# qo-100-pa-bias-controller.net
KiCad netlist of a schematic drawn in EAGLE
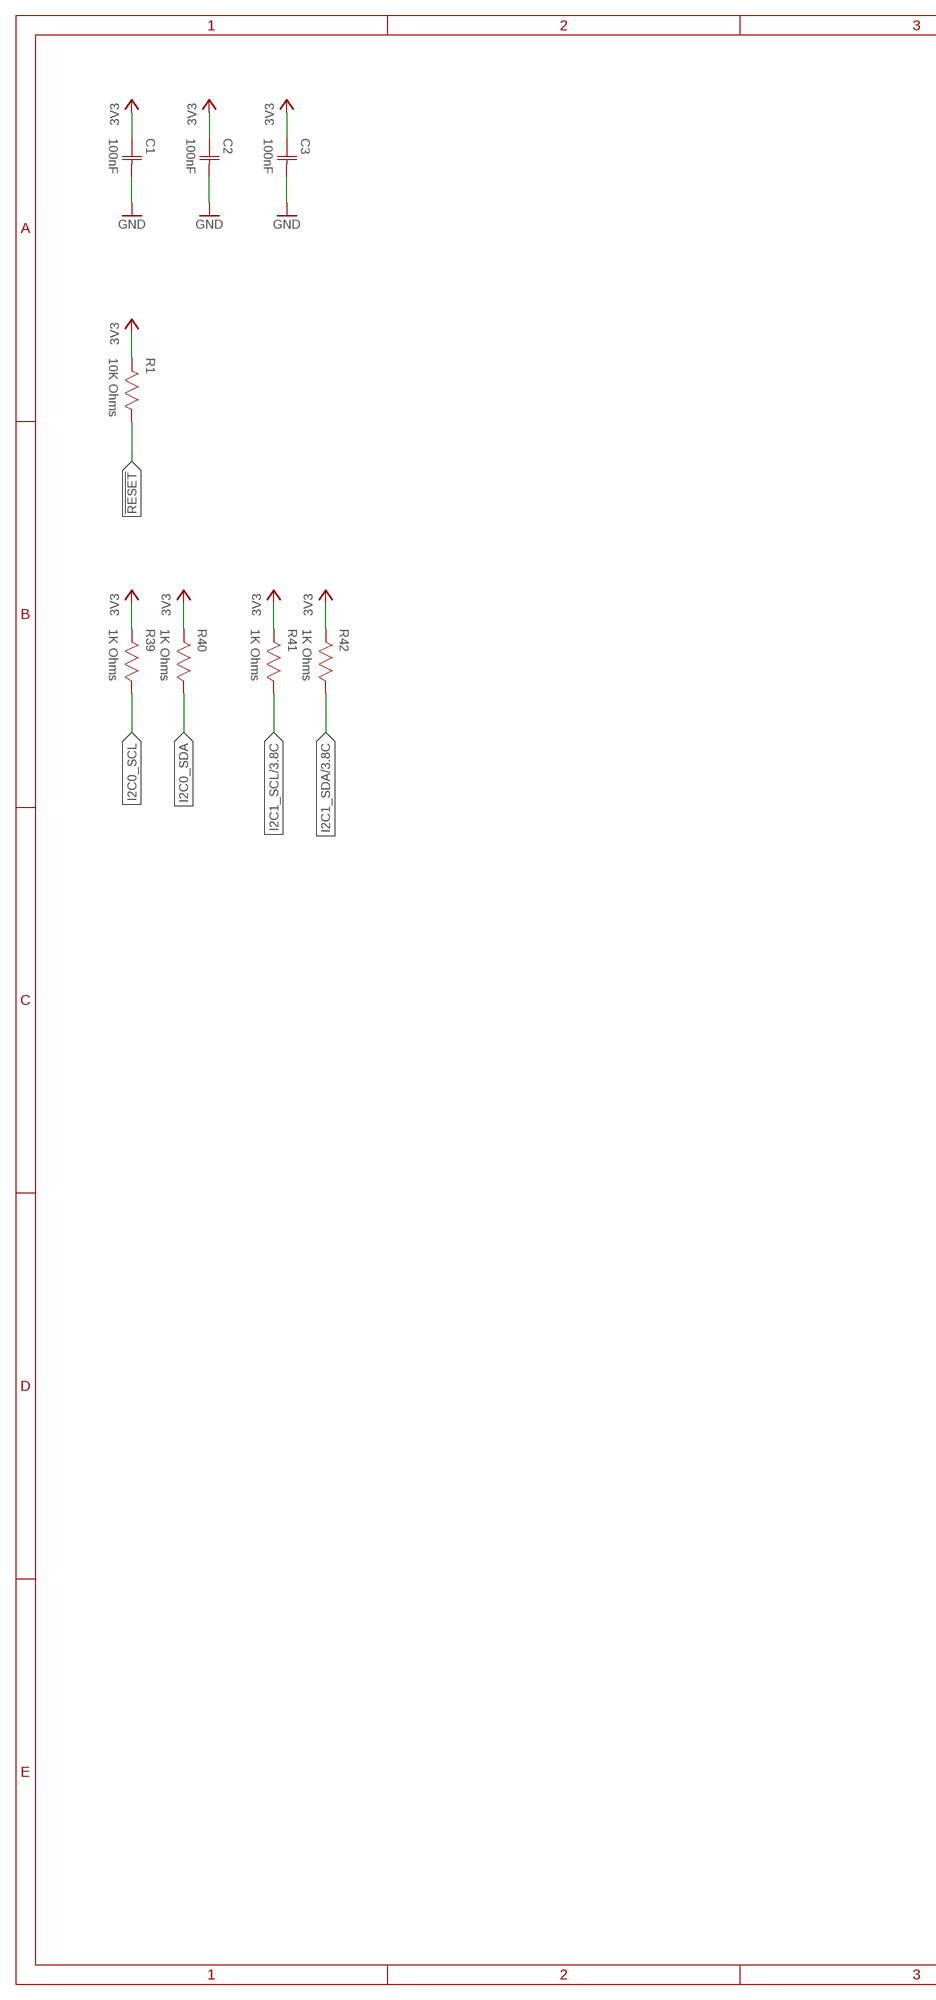
[diagram p0: schematic, sheet 1, part 1 of 2]
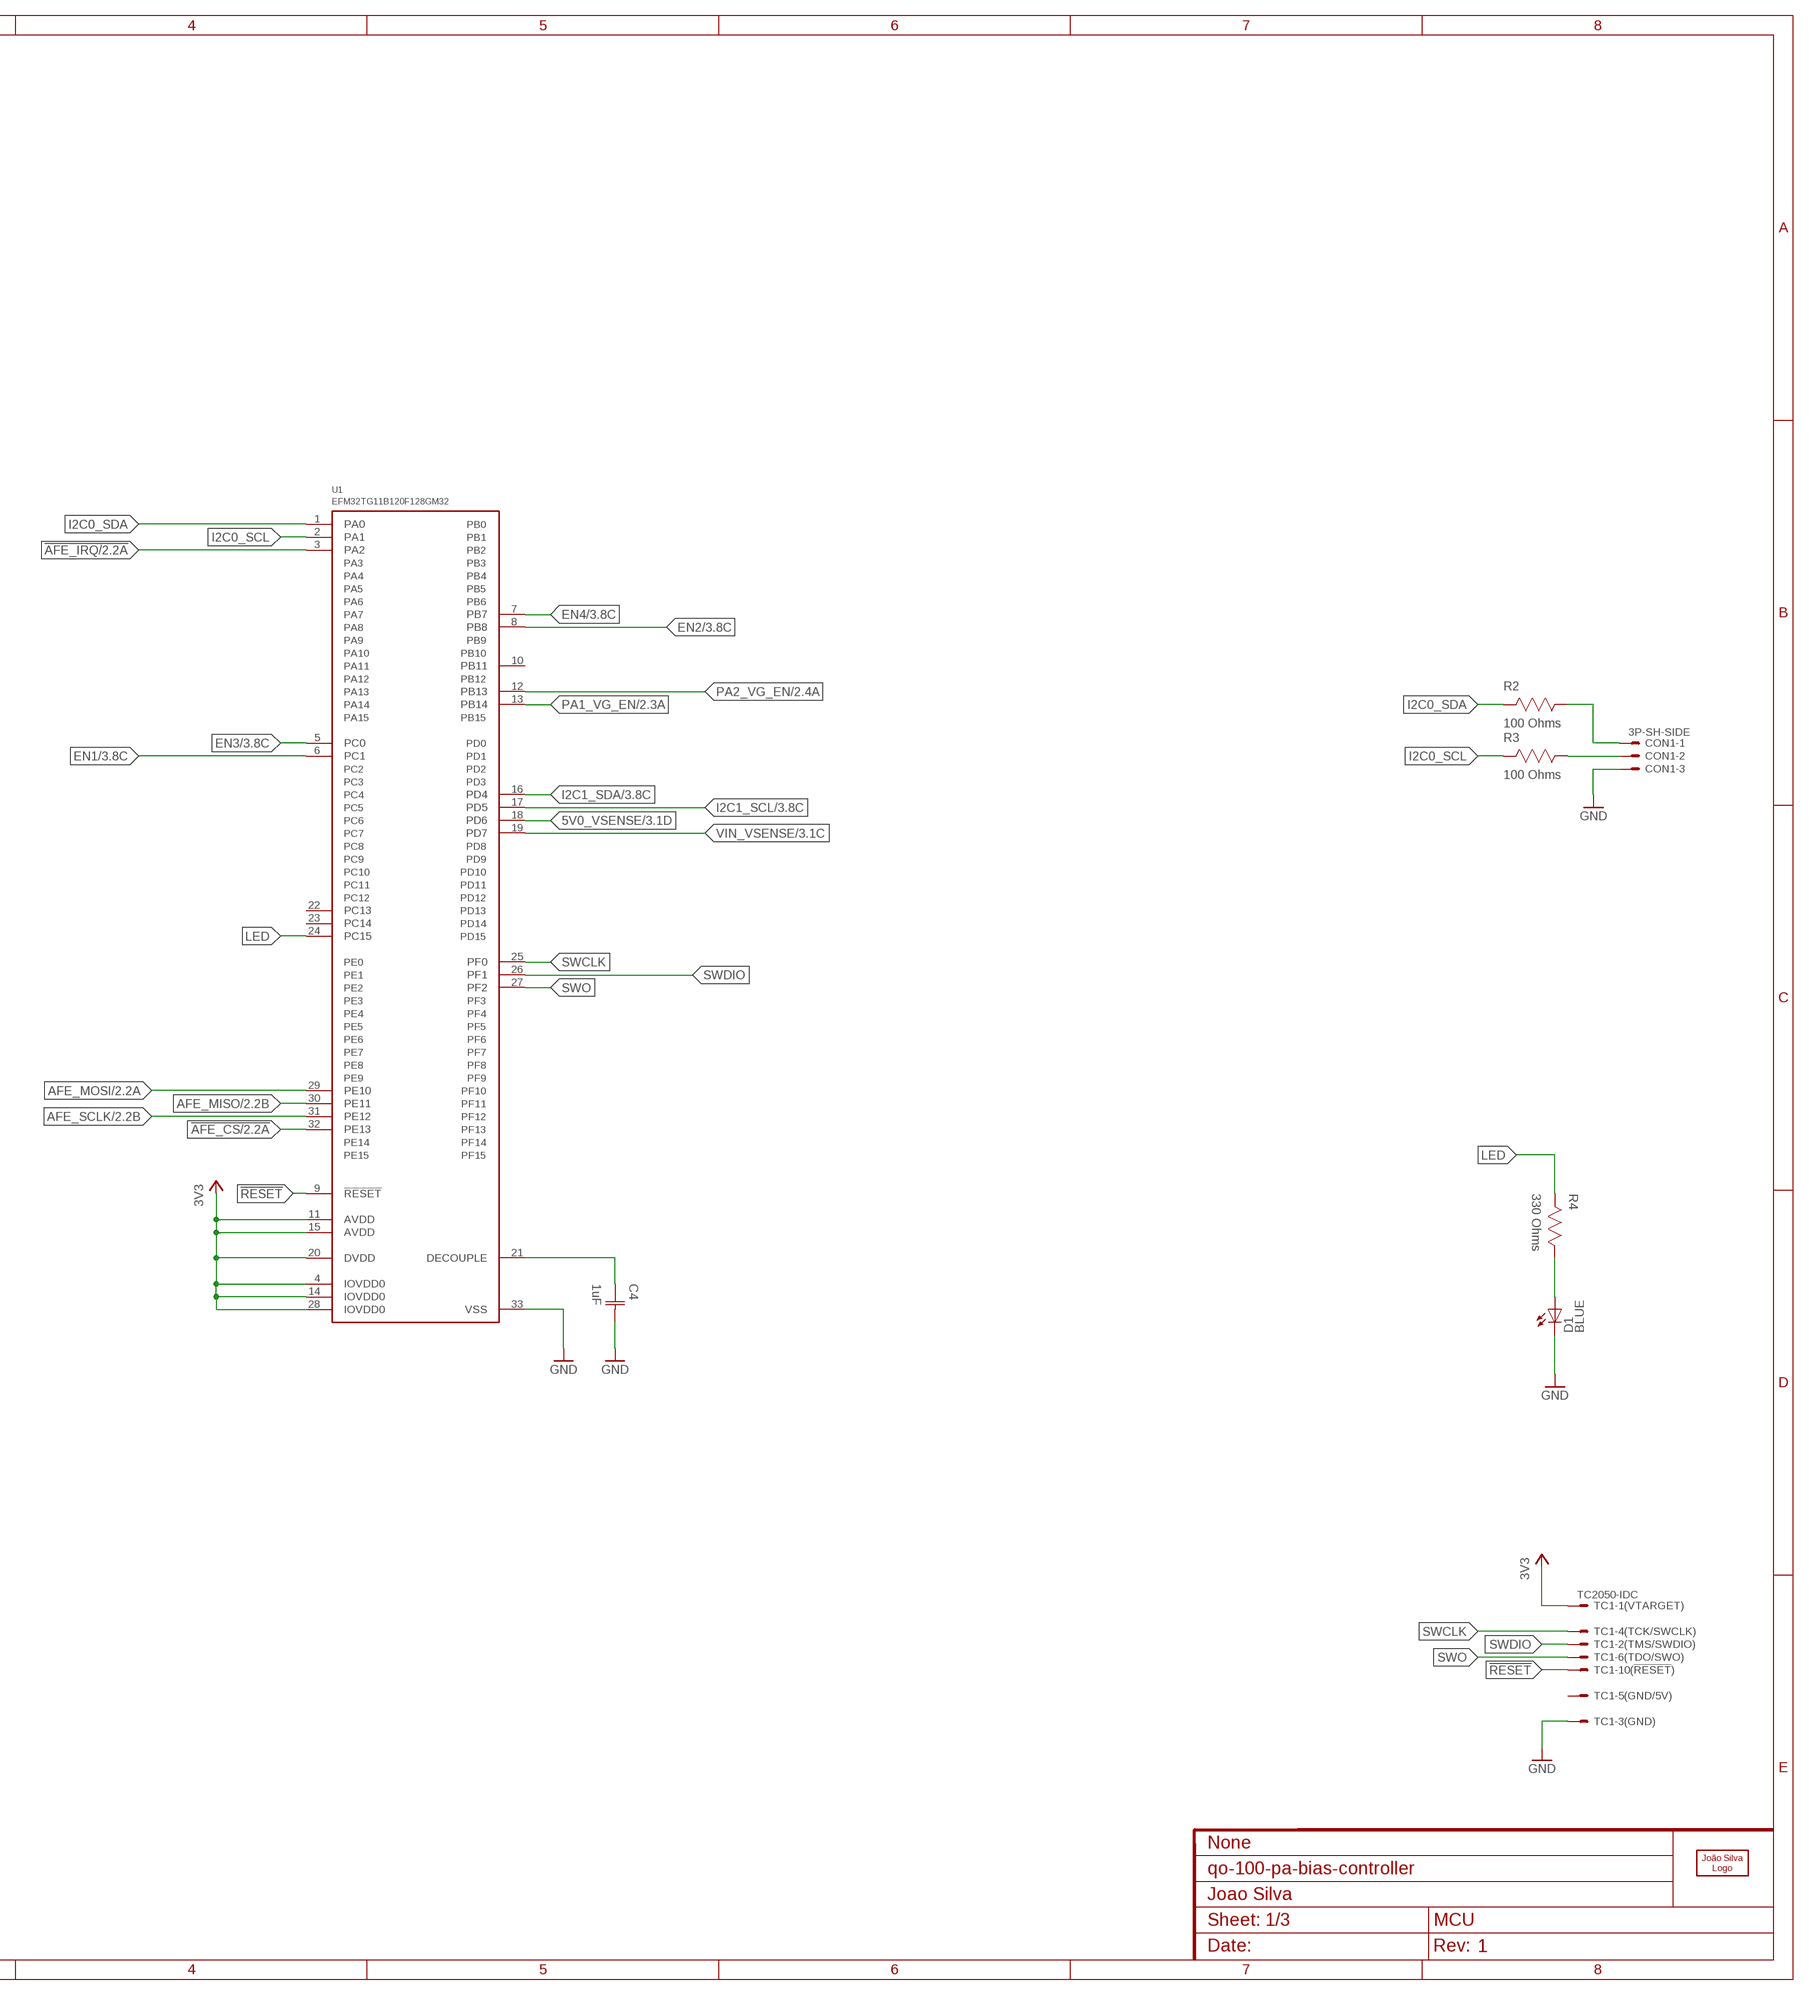
[diagram p1: schematic, sheet 1, part 2 of 2]
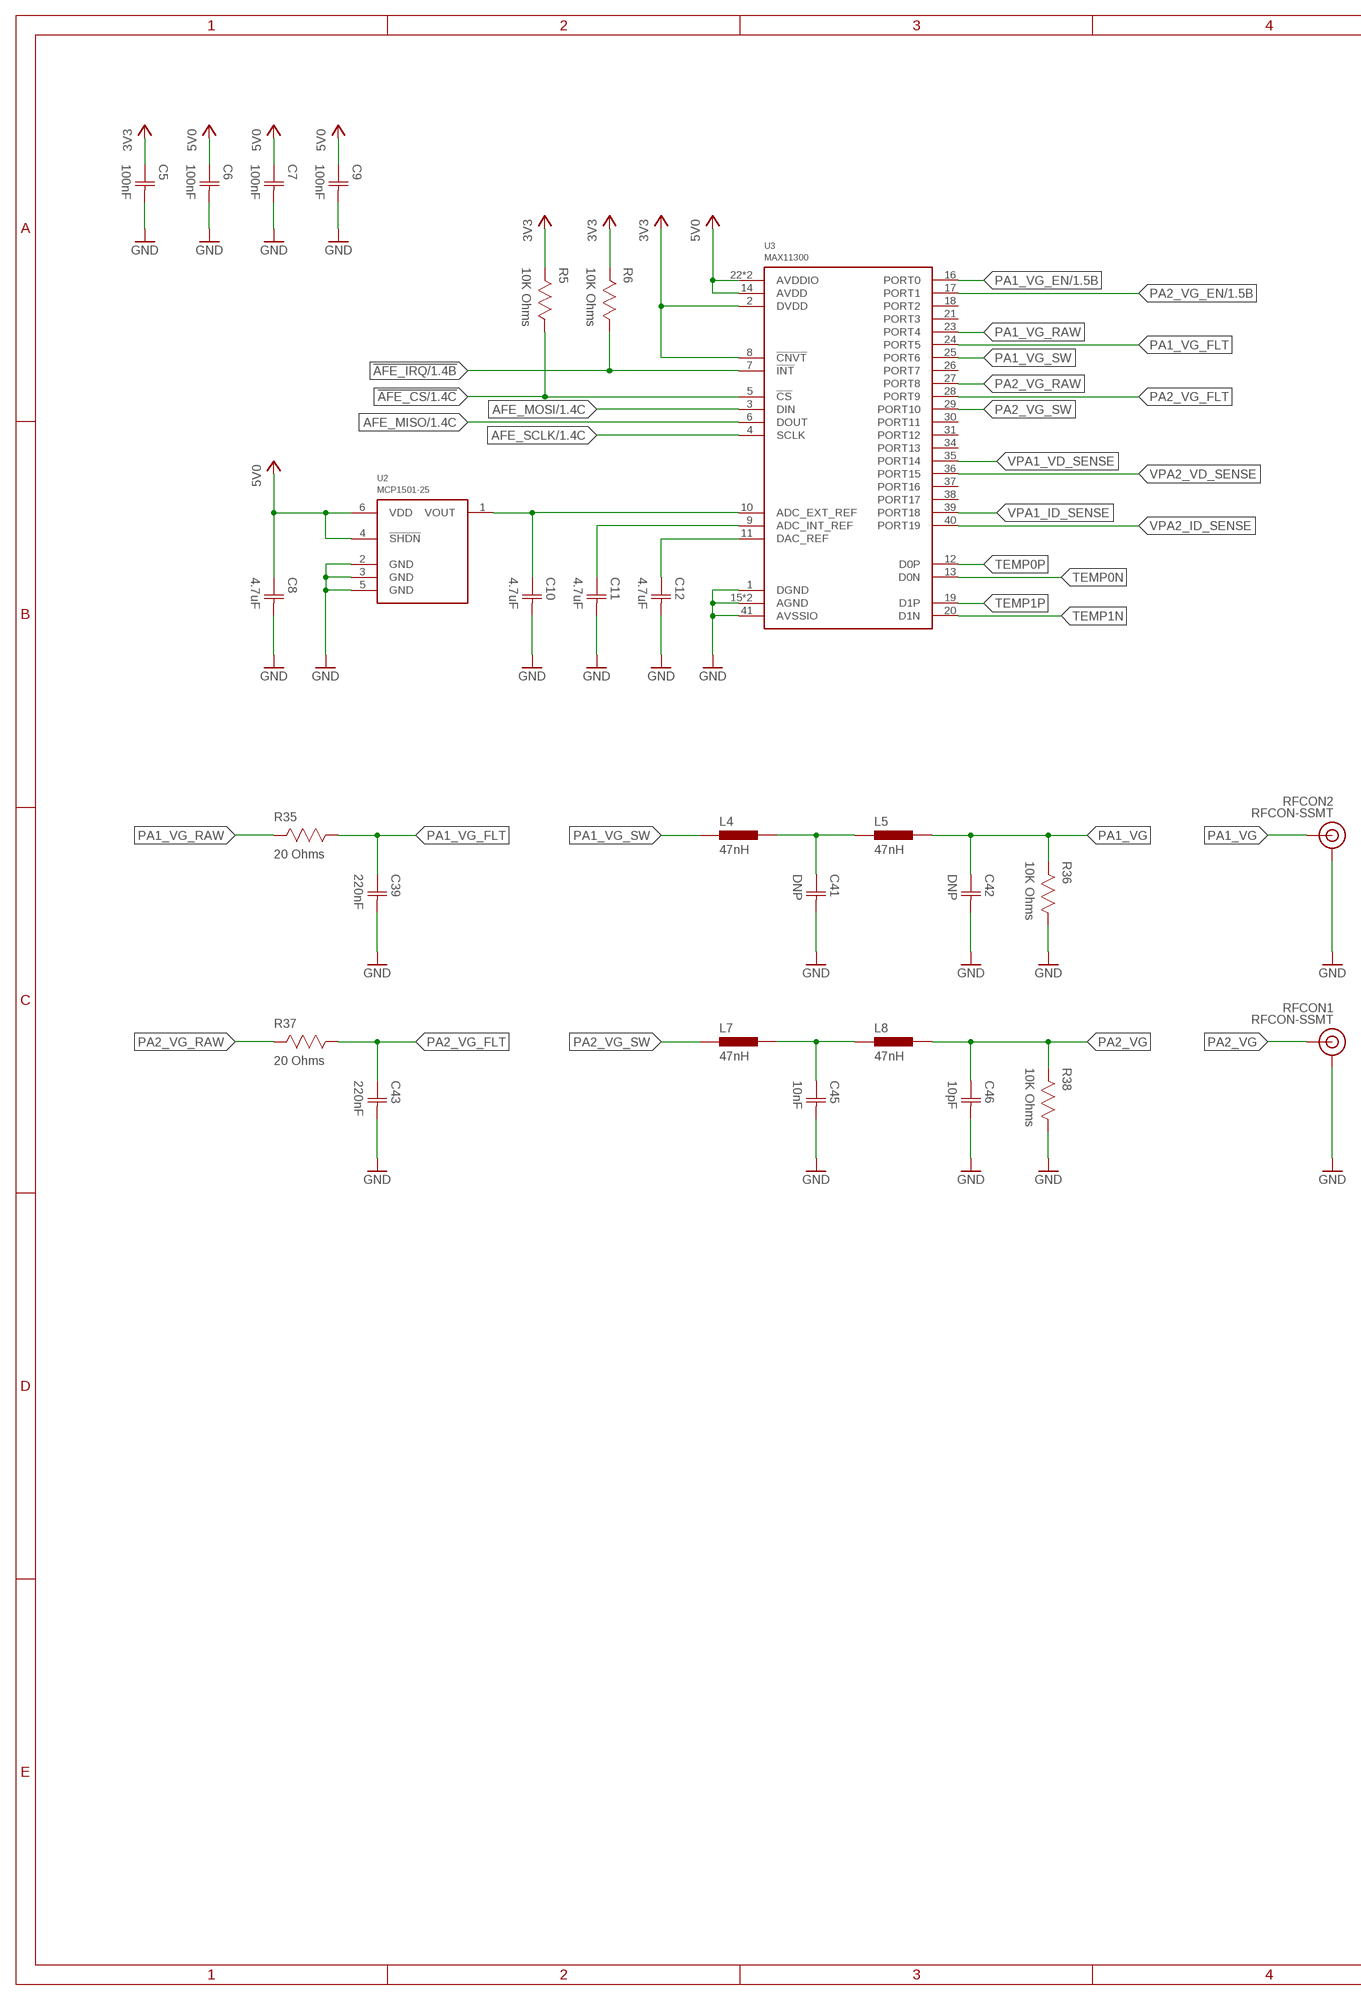
[diagram p2: schematic, sheet 2, part 1 of 2]
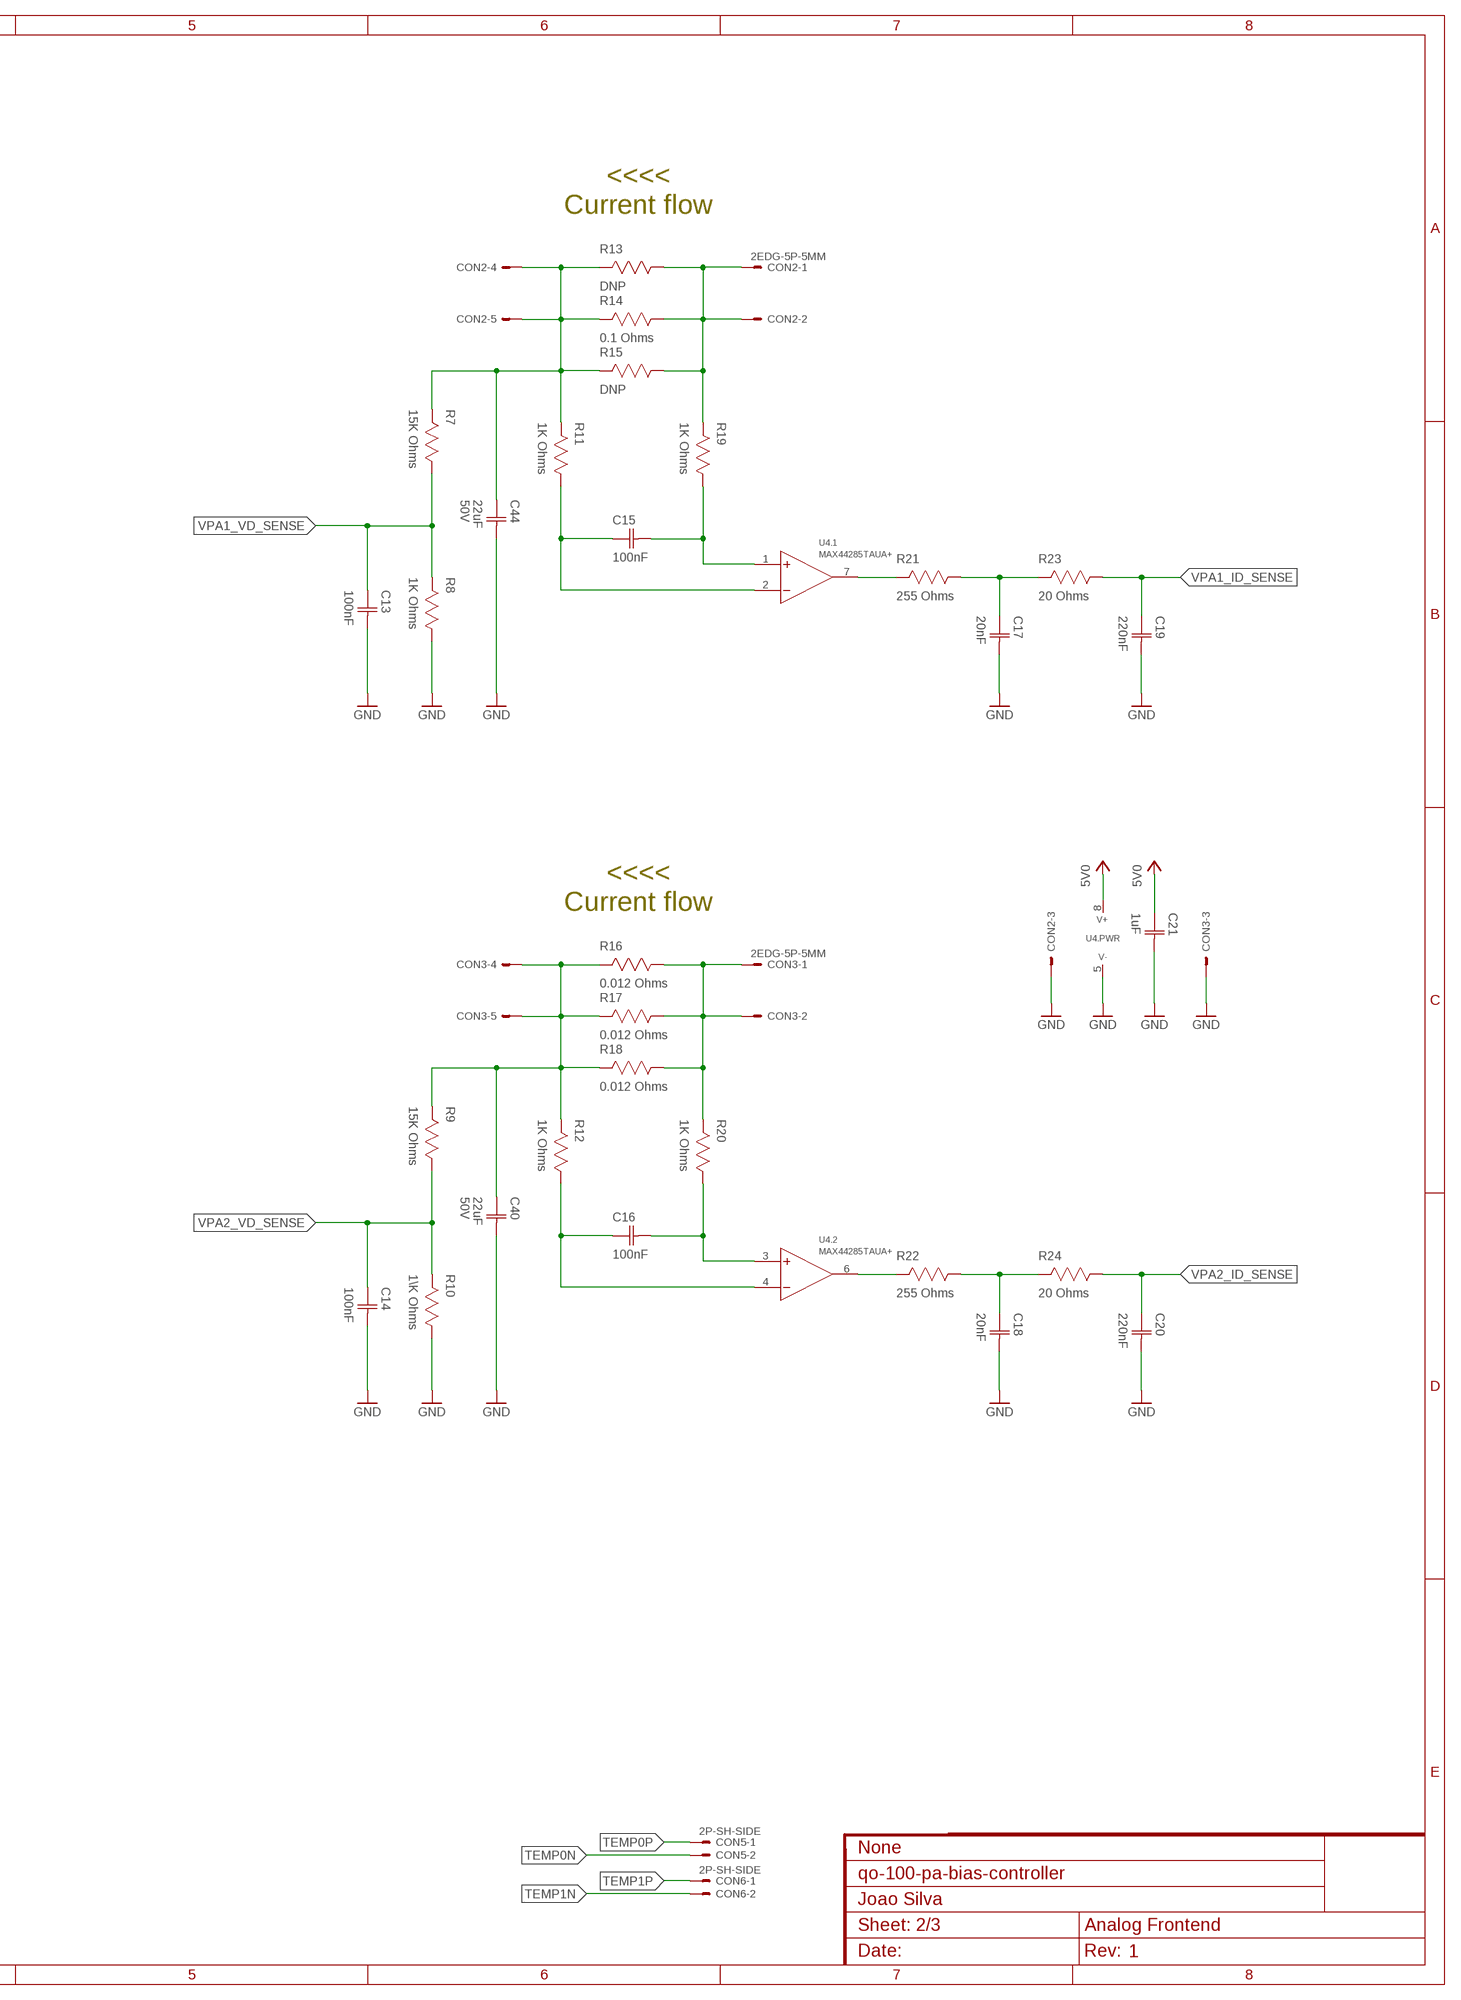
[diagram p3: schematic, sheet 2, part 2 of 2]
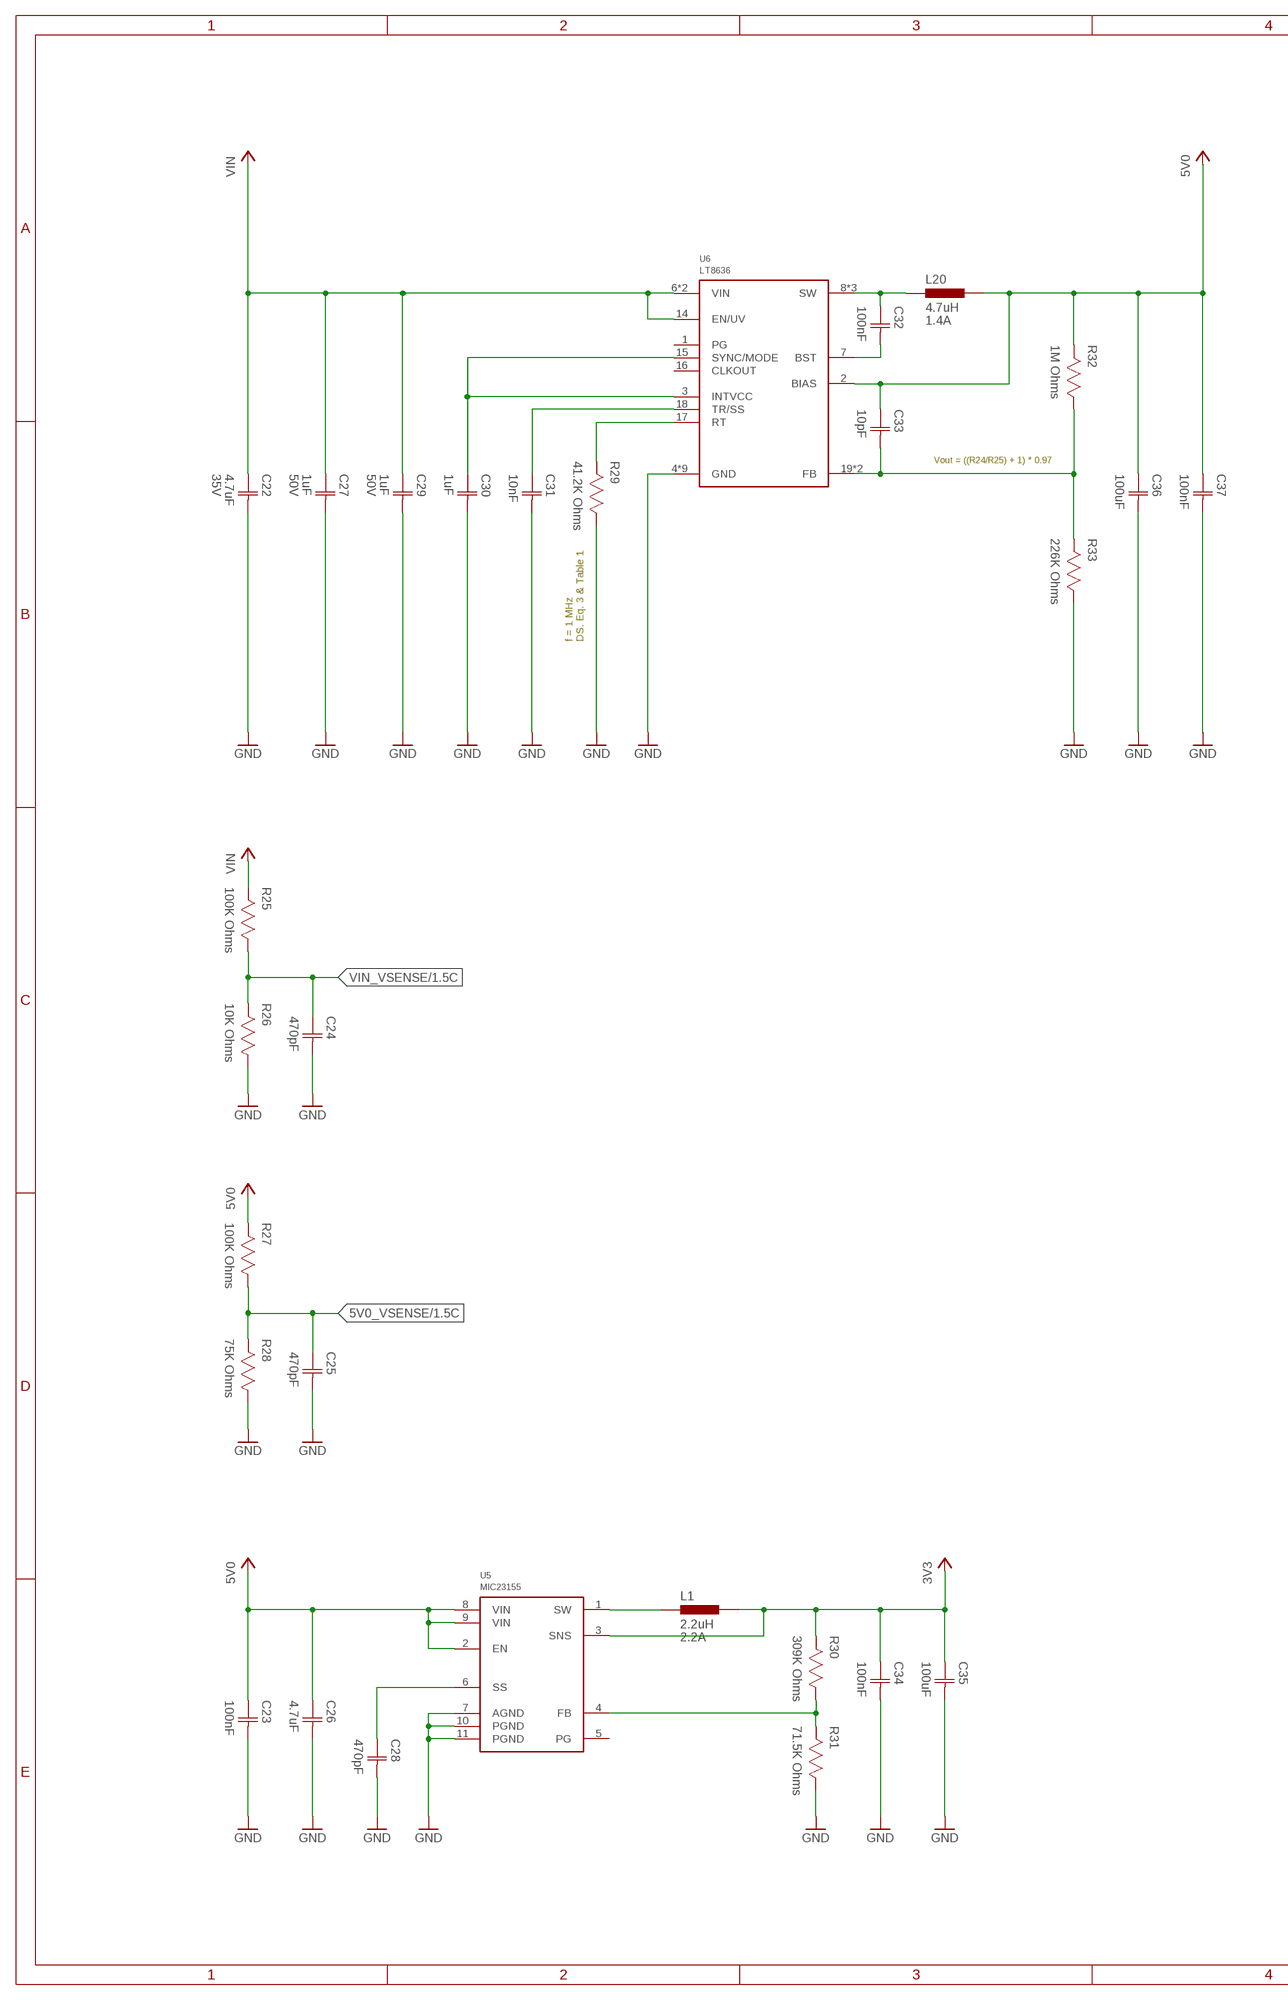
[diagram p4: schematic, sheet 3, part 1 of 2]
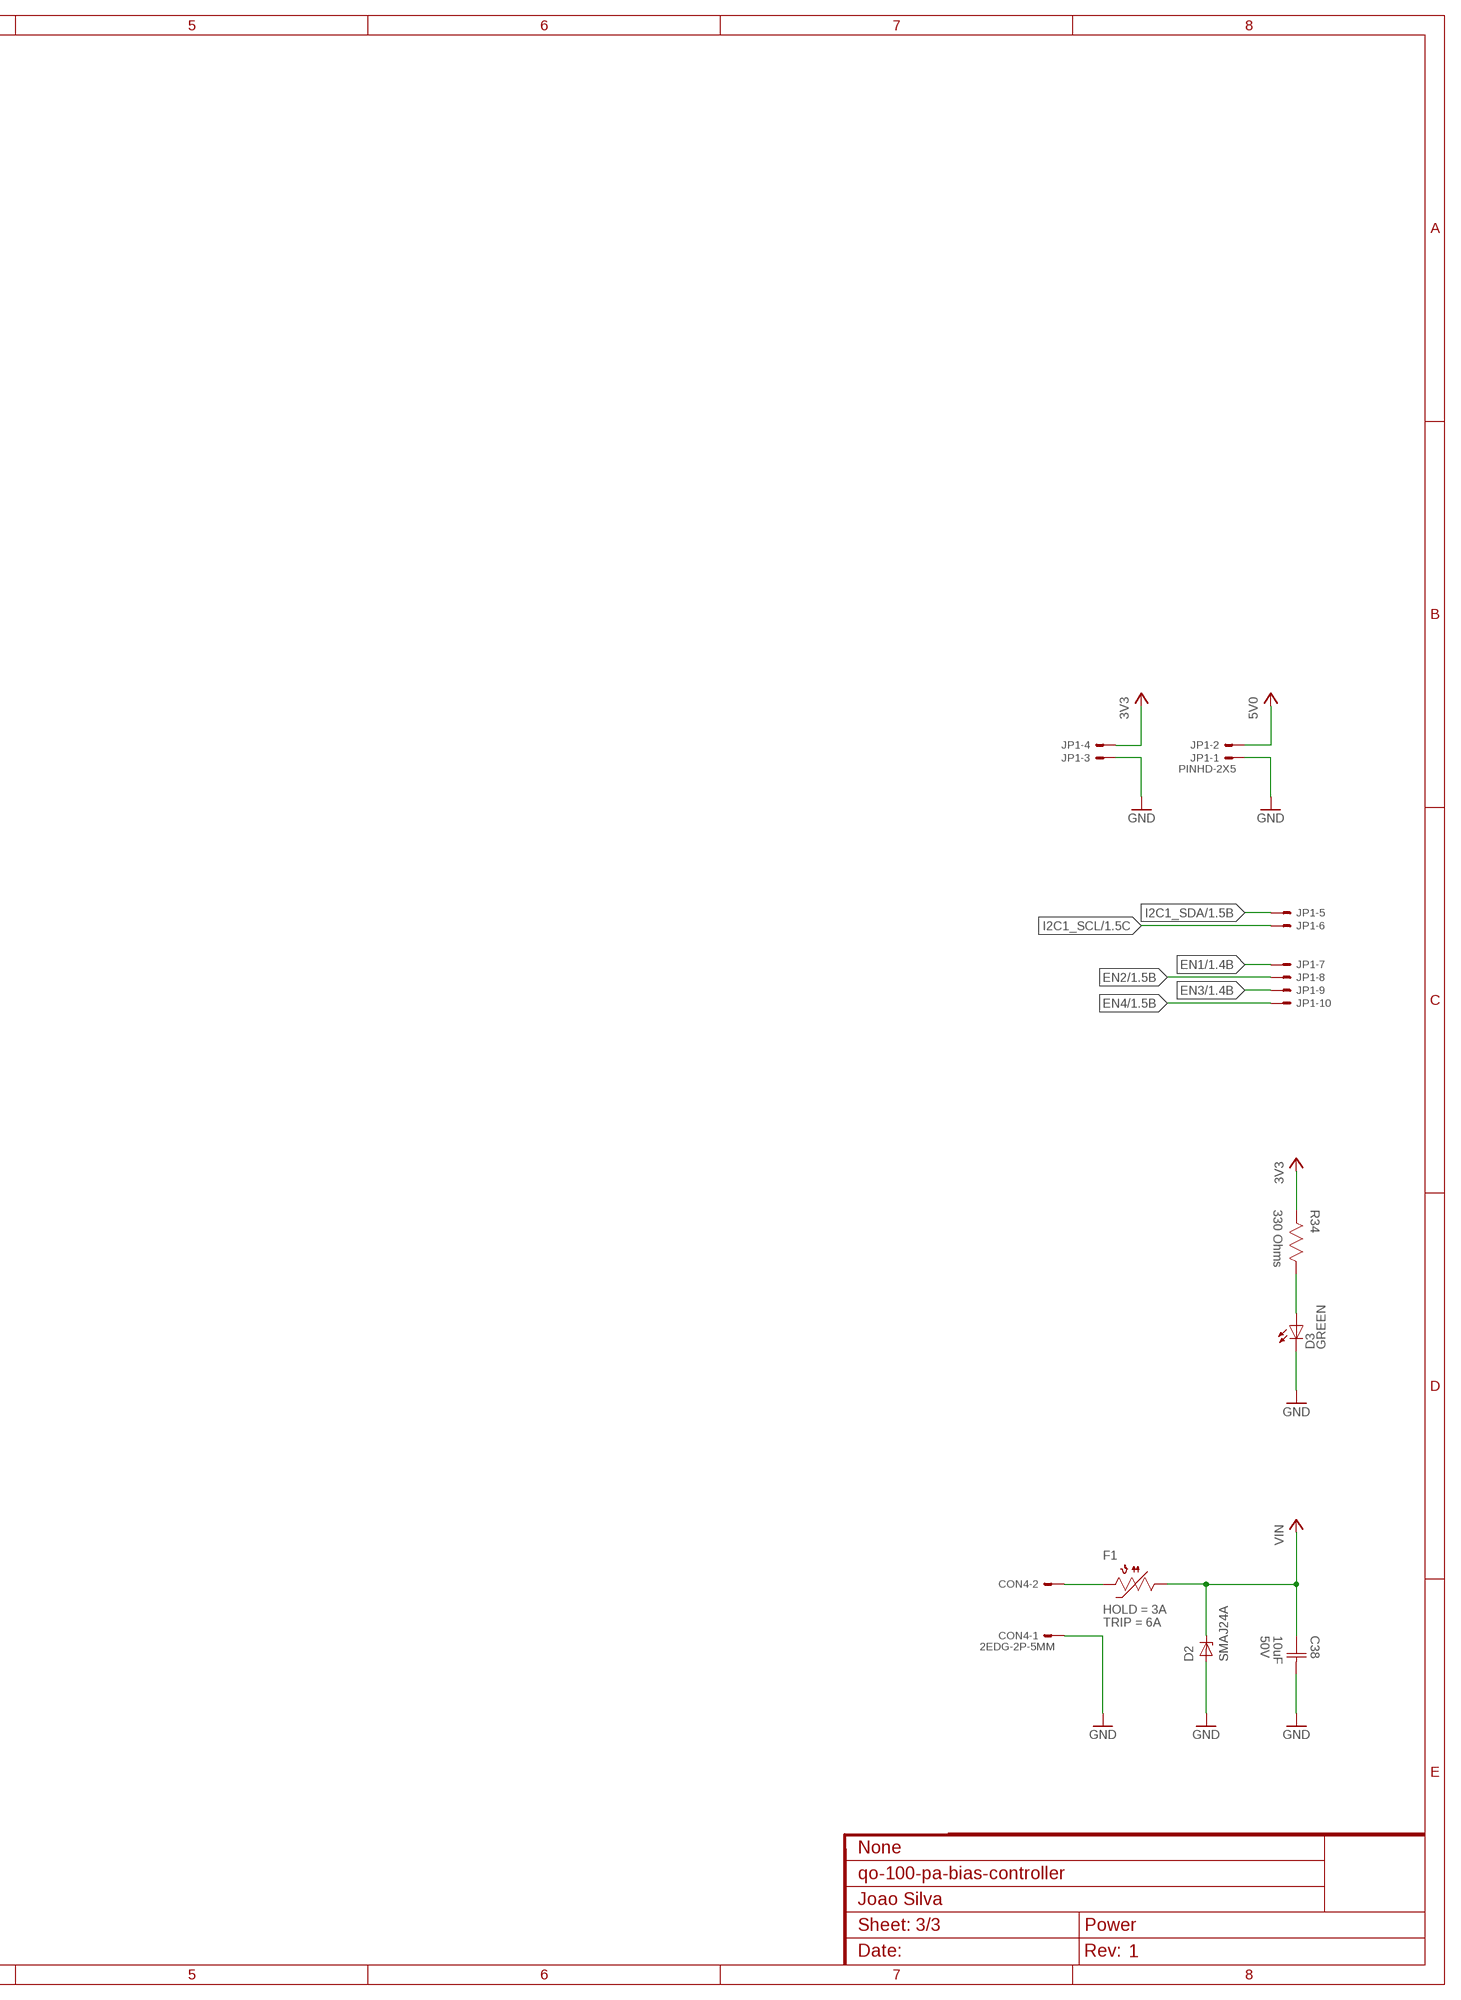
[diagram p5: schematic, sheet 3, part 2 of 2]

(export (version "E")
  (design (tool "Eeschema 10.0.6"))
  (components
    (comp (ref "C5")
      (value "100nF")
      (footprint "eagle-import:CAP0603")
      (libsource (lib "eagle-import") (part "CAPACITOR-0603"))
    )
    (comp (ref "C6")
      (value "100nF")
      (footprint "eagle-import:CAP0603")
      (libsource (lib "eagle-import") (part "CAPACITOR-0603"))
    )
    (comp (ref "C7")
      (value "100nF")
      (footprint "eagle-import:CAP0603")
      (libsource (lib "eagle-import") (part "CAPACITOR-0603"))
    )
    (comp (ref "C8")
      (value "4.7uF")
      (footprint "eagle-import:CAP0603")
      (libsource (lib "eagle-import") (part "CAPACITOR-0603"))
    )
    (comp (ref "C9")
      (value "100nF")
      (footprint "eagle-import:CAP0603")
      (libsource (lib "eagle-import") (part "CAPACITOR-0603"))
    )
    (comp (ref "C10")
      (value "4.7uF")
      (footprint "eagle-import:CAP0603")
      (libsource (lib "eagle-import") (part "CAPACITOR-0603"))
    )
    (comp (ref "C11")
      (value "4.7uF")
      (footprint "eagle-import:CAP0603")
      (libsource (lib "eagle-import") (part "CAPACITOR-0603"))
    )
    (comp (ref "C12")
      (value "4.7uF")
      (footprint "eagle-import:CAP0603")
      (libsource (lib "eagle-import") (part "CAPACITOR-0603"))
    )
    (comp (ref "C13")
      (value "100nF")
      (footprint "eagle-import:CAP0603")
      (libsource (lib "eagle-import") (part "CAPACITOR-0603"))
    )
    (comp (ref "C14")
      (value "100nF")
      (footprint "eagle-import:CAP0603")
      (libsource (lib "eagle-import") (part "CAPACITOR-0603"))
    )
    (comp (ref "C15")
      (value "100nF")
      (footprint "eagle-import:CAP0603")
      (libsource (lib "eagle-import") (part "CAPACITOR-0603"))
    )
    (comp (ref "C16")
      (value "100nF")
      (footprint "eagle-import:CAP0603")
      (libsource (lib "eagle-import") (part "CAPACITOR-0603"))
    )
    (comp (ref "C17")
      (value "20nF")
      (footprint "eagle-import:CAP0603")
      (libsource (lib "eagle-import") (part "CAPACITOR-0603"))
    )
    (comp (ref "C18")
      (value "20nF")
      (footprint "eagle-import:CAP0603")
      (libsource (lib "eagle-import") (part "CAPACITOR-0603"))
    )
    (comp (ref "C19")
      (value "220nF")
      (footprint "eagle-import:CAP0603")
      (libsource (lib "eagle-import") (part "CAPACITOR-0603"))
    )
    (comp (ref "C20")
      (value "220nF")
      (footprint "eagle-import:CAP0603")
      (libsource (lib "eagle-import") (part "CAPACITOR-0603"))
    )
    (comp (ref "C21")
      (value "1uF")
      (footprint "eagle-import:CAP0603")
      (libsource (lib "eagle-import") (part "CAPACITOR-0603"))
    )
    (comp (ref "C39")
      (value "220nF")
      (footprint "eagle-import:CAP0603")
      (libsource (lib "eagle-import") (part "CAPACITOR-0603"))
    )
    (comp (ref "C40")
      (value "22uF")
      (footprint "eagle-import:CAP2220")
      (fields (field (name "VOLTAGE") "50V"))
      (libsource (lib "eagle-import") (part "CAPACITOR-2220"))
    )
    (comp (ref "C41")
      (value "DNP")
      (footprint "eagle-import:CAP0603")
      (libsource (lib "eagle-import") (part "CAPACITOR-0603"))
    )
    (comp (ref "C42")
      (value "DNP")
      (footprint "eagle-import:CAP0603")
      (libsource (lib "eagle-import") (part "CAPACITOR-0603"))
    )
    (comp (ref "C43")
      (value "220nF")
      (footprint "eagle-import:CAP0603")
      (libsource (lib "eagle-import") (part "CAPACITOR-0603"))
    )
    (comp (ref "C44")
      (value "22uF")
      (footprint "eagle-import:CAP2220")
      (fields (field (name "VOLTAGE") "50V"))
      (libsource (lib "eagle-import") (part "CAPACITOR-2220"))
    )
    (comp (ref "C45")
      (value "10nF")
      (footprint "eagle-import:CAP0603")
      (libsource (lib "eagle-import") (part "CAPACITOR-0603"))
    )
    (comp (ref "C46")
      (value "10pF")
      (footprint "eagle-import:CAP0603")
      (libsource (lib "eagle-import") (part "CAPACITOR-0603"))
    )
    (comp (ref "CON2")
      (value "2EDG-5P-5MM")
      (footprint "eagle-import:2EDG-5P-5MM")
      (libsource (lib "eagle-import") (part "2EDG-5P-5MM"))
    )
    (comp (ref "CON3")
      (value "2EDG-5P-5MM")
      (footprint "eagle-import:2EDG-5P-5MM")
      (libsource (lib "eagle-import") (part "2EDG-5P-5MM"))
    )
    (comp (ref "CON5")
      (value "2P-SH-SIDE")
      (footprint "eagle-import:SH-02-SIDE")
      (libsource (lib "eagle-import") (part "2P-SH-SIDE"))
    )
    (comp (ref "CON6")
      (value "2P-SH-SIDE")
      (footprint "eagle-import:SH-02-SIDE")
      (libsource (lib "eagle-import") (part "2P-SH-SIDE"))
    )
    (comp (ref "L4")
      (value "47nH")
      (footprint "eagle-import:IND0603")
      (libsource (lib "eagle-import") (part "INDUCTOR-0603"))
    )
    (comp (ref "L5")
      (value "47nH")
      (footprint "eagle-import:IND0603")
      (libsource (lib "eagle-import") (part "INDUCTOR-0603"))
    )
    (comp (ref "L7")
      (value "47nH")
      (footprint "eagle-import:IND0603")
      (libsource (lib "eagle-import") (part "INDUCTOR-0603"))
    )
    (comp (ref "L8")
      (value "47nH")
      (footprint "eagle-import:IND0603")
      (libsource (lib "eagle-import") (part "INDUCTOR-0603"))
    )
    (comp (ref "R5")
      (value "10K Ohms")
      (footprint "eagle-import:RES0603")
      (libsource (lib "eagle-import") (part "RESISTOR-0603"))
    )
    (comp (ref "R6")
      (value "10K Ohms")
      (footprint "eagle-import:RES0603")
      (libsource (lib "eagle-import") (part "RESISTOR-0603"))
    )
    (comp (ref "R7")
      (value "15K Ohms")
      (footprint "eagle-import:RES0603")
      (libsource (lib "eagle-import") (part "RESISTOR-0603"))
    )
    (comp (ref "R8")
      (value "1K Ohms")
      (footprint "eagle-import:RES0603")
      (libsource (lib "eagle-import") (part "RESISTOR-0603"))
    )
    (comp (ref "R9")
      (value "15K Ohms")
      (footprint "eagle-import:RES0603")
      (libsource (lib "eagle-import") (part "RESISTOR-0603"))
    )
    (comp (ref "R10")
      (value "1\\K Ohms")
      (footprint "eagle-import:RES0603")
      (libsource (lib "eagle-import") (part "RESISTOR-0603"))
    )
    (comp (ref "R11")
      (value "1K Ohms")
      (footprint "eagle-import:RES0603")
      (libsource (lib "eagle-import") (part "RESISTOR-0603"))
    )
    (comp (ref "R12")
      (value "1K Ohms")
      (footprint "eagle-import:RES0603")
      (libsource (lib "eagle-import") (part "RESISTOR-0603"))
    )
    (comp (ref "R13")
      (value "DNP")
      (footprint "eagle-import:RES2512")
      (libsource (lib "eagle-import") (part "RESISTOR-2512"))
    )
    (comp (ref "R14")
      (value "0.1 Ohms")
      (footprint "eagle-import:RES2512")
      (libsource (lib "eagle-import") (part "RESISTOR-2512"))
    )
    (comp (ref "R15")
      (value "DNP")
      (footprint "eagle-import:RES2512")
      (libsource (lib "eagle-import") (part "RESISTOR-2512"))
    )
    (comp (ref "R16")
      (value "0.012 Ohms")
      (footprint "eagle-import:RES2512")
      (libsource (lib "eagle-import") (part "RESISTOR-2512"))
    )
    (comp (ref "R17")
      (value "0.012 Ohms")
      (footprint "eagle-import:RES2512")
      (libsource (lib "eagle-import") (part "RESISTOR-2512"))
    )
    (comp (ref "R18")
      (value "0.012 Ohms")
      (footprint "eagle-import:RES2512")
      (libsource (lib "eagle-import") (part "RESISTOR-2512"))
    )
    (comp (ref "R19")
      (value "1K Ohms")
      (footprint "eagle-import:RES0603")
      (libsource (lib "eagle-import") (part "RESISTOR-0603"))
    )
    (comp (ref "R20")
      (value "1K Ohms")
      (footprint "eagle-import:RES0603")
      (libsource (lib "eagle-import") (part "RESISTOR-0603"))
    )
    (comp (ref "R21")
      (value "255 Ohms")
      (footprint "eagle-import:RES0603")
      (libsource (lib "eagle-import") (part "RESISTOR-0603"))
    )
    (comp (ref "R22")
      (value "255 Ohms")
      (footprint "eagle-import:RES0603")
      (libsource (lib "eagle-import") (part "RESISTOR-0603"))
    )
    (comp (ref "R23")
      (value "20 Ohms")
      (footprint "eagle-import:RES0603")
      (libsource (lib "eagle-import") (part "RESISTOR-0603"))
    )
    (comp (ref "R24")
      (value "20 Ohms")
      (footprint "eagle-import:RES0603")
      (libsource (lib "eagle-import") (part "RESISTOR-0603"))
    )
    (comp (ref "R35")
      (value "20 Ohms")
      (footprint "eagle-import:RES0603")
      (libsource (lib "eagle-import") (part "RESISTOR-0603"))
    )
    (comp (ref "R36")
      (value "10K Ohms")
      (footprint "eagle-import:RES0603")
      (libsource (lib "eagle-import") (part "RESISTOR-0603"))
    )
    (comp (ref "R37")
      (value "20 Ohms")
      (footprint "eagle-import:RES0603")
      (libsource (lib "eagle-import") (part "RESISTOR-0603"))
    )
    (comp (ref "R38")
      (value "10K Ohms")
      (footprint "eagle-import:RES0603")
      (libsource (lib "eagle-import") (part "RESISTOR-0603"))
    )
    (comp (ref "RFCON1")
      (value "RFCON-SSMT")
      (footprint "eagle-import:SSMT")
      (libsource (lib "eagle-import") (part "RFCON-SSMT"))
    )
    (comp (ref "RFCON2")
      (value "RFCON-SSMT")
      (footprint "eagle-import:SSMT")
      (libsource (lib "eagle-import") (part "RFCON-SSMT"))
    )
    (comp (ref "U2")
      (value "MCP1501-25")
      (footprint "eagle-import:SOT23-6")
      (libsource (lib "eagle-import") (part "MCP1501-25"))
    )
    (comp (ref "U3")
      (value "MAX11300")
      (footprint "eagle-import:QFN40")
      (libsource (lib "eagle-import") (part "MAX11300"))
    )
    (comp (ref "U4")
      (value "MAX44285TAUA+")
      (footprint "eagle-import:MSOP8")
      (libsource (lib "eagle-import") (part "MAX44285AUA+T"))
    )
    (comp (ref "C1")
      (value "100nF")
      (footprint "eagle-import:CAP0603")
      (libsource (lib "eagle-import") (part "CAPACITOR-0603"))
    )
    (comp (ref "C2")
      (value "100nF")
      (footprint "eagle-import:CAP0603")
      (libsource (lib "eagle-import") (part "CAPACITOR-0603"))
    )
    (comp (ref "C3")
      (value "100nF")
      (footprint "eagle-import:CAP0603")
      (libsource (lib "eagle-import") (part "CAPACITOR-0603"))
    )
    (comp (ref "C4")
      (value "1uF")
      (footprint "eagle-import:CAP0603")
      (libsource (lib "eagle-import") (part "CAPACITOR-0603"))
    )
    (comp (ref "CON1")
      (value "3P-SH-SIDE")
      (footprint "eagle-import:SH-03-SIDE")
      (libsource (lib "eagle-import") (part "3P-SH-SIDE"))
    )
    (comp (ref "D1")
      (value "LED0603")
      (footprint "eagle-import:0603")
      (fields (field (name "COLOR") "BLUE"))
      (libsource (lib "eagle-import") (part "LED0603"))
    )
    (comp (ref "LOGO1")
      (value "JS-10MM")
      (footprint "eagle-import:JS_10MM")
      (libsource (lib "eagle-import") (part "JS-10MM"))
    )
    (comp (ref "R1")
      (value "10K Ohms")
      (footprint "eagle-import:RES0603")
      (libsource (lib "eagle-import") (part "RESISTOR-0603"))
    )
    (comp (ref "R2")
      (value "100 Ohms")
      (footprint "eagle-import:RES0603")
      (libsource (lib "eagle-import") (part "RESISTOR-0603"))
    )
    (comp (ref "R3")
      (value "100 Ohms")
      (footprint "eagle-import:RES0603")
      (libsource (lib "eagle-import") (part "RESISTOR-0603"))
    )
    (comp (ref "R4")
      (value "330 Ohms")
      (footprint "eagle-import:RES0603")
      (libsource (lib "eagle-import") (part "RESISTOR-0603"))
    )
    (comp (ref "R39")
      (value "1K Ohms")
      (footprint "eagle-import:RES0603")
      (libsource (lib "eagle-import") (part "RESISTOR-0603"))
    )
    (comp (ref "R40")
      (value "1K Ohms")
      (footprint "eagle-import:RES0603")
      (libsource (lib "eagle-import") (part "RESISTOR-0603"))
    )
    (comp (ref "R41")
      (value "1K Ohms")
      (footprint "eagle-import:RES0603")
      (libsource (lib "eagle-import") (part "RESISTOR-0603"))
    )
    (comp (ref "R42")
      (value "1K Ohms")
      (footprint "eagle-import:RES0603")
      (libsource (lib "eagle-import") (part "RESISTOR-0603"))
    )
    (comp (ref "TC1")
      (value "TC2050-IDC")
      (footprint "eagle-import:TC2050-IDC")
      (libsource (lib "eagle-import") (part "TC2050-IDC"))
    )
    (comp (ref "U1")
      (value "EFM32TG11B120F128GM32")
      (footprint "eagle-import:QFN32_0.5P_TG")
      (libsource (lib "eagle-import") (part "EFM32TG11B1M3220F128G"))
    )
    (comp (ref "C22")
      (value "4.7uF")
      (footprint "eagle-import:CAP0603")
      (fields (field (name "VOLTAGE") "35V"))
      (libsource (lib "eagle-import") (part "CAPACITOR-0603"))
    )
    (comp (ref "C23")
      (value "100nF")
      (footprint "eagle-import:CAP0603")
      (libsource (lib "eagle-import") (part "CAPACITOR-0603"))
    )
    (comp (ref "C24")
      (value "470pF")
      (footprint "eagle-import:CAP0603")
      (libsource (lib "eagle-import") (part "CAPACITOR-0603"))
    )
    (comp (ref "C25")
      (value "470pF")
      (footprint "eagle-import:CAP0603")
      (libsource (lib "eagle-import") (part "CAPACITOR-0603"))
    )
    (comp (ref "C26")
      (value "4.7uF")
      (footprint "eagle-import:CAP0603")
      (libsource (lib "eagle-import") (part "CAPACITOR-0603"))
    )
    (comp (ref "C27")
      (value "1uF")
      (footprint "eagle-import:CAP0603")
      (fields (field (name "VOLTAGE") "50V"))
      (libsource (lib "eagle-import") (part "CAPACITOR-0603"))
    )
    (comp (ref "C28")
      (value "470pF")
      (footprint "eagle-import:CAP0603")
      (libsource (lib "eagle-import") (part "CAPACITOR-0603"))
    )
    (comp (ref "C29")
      (value "1uF")
      (footprint "eagle-import:CAP0603")
      (fields (field (name "VOLTAGE") "50V"))
      (libsource (lib "eagle-import") (part "CAPACITOR-0603"))
    )
    (comp (ref "C30")
      (value "1uF")
      (footprint "eagle-import:CAP0603")
      (libsource (lib "eagle-import") (part "CAPACITOR-0603"))
    )
    (comp (ref "C31")
      (value "10nF")
      (footprint "eagle-import:CAP0603")
      (libsource (lib "eagle-import") (part "CAPACITOR-0603"))
    )
    (comp (ref "C32")
      (value "100nF")
      (footprint "eagle-import:CAP0603")
      (libsource (lib "eagle-import") (part "CAPACITOR-0603"))
    )
    (comp (ref "C33")
      (value "10pF")
      (footprint "eagle-import:CAP0603")
      (libsource (lib "eagle-import") (part "CAPACITOR-0603"))
    )
    (comp (ref "C34")
      (value "100nF")
      (footprint "eagle-import:CAP0603")
      (libsource (lib "eagle-import") (part "CAPACITOR-0603"))
    )
    (comp (ref "C35")
      (value "100uF")
      (footprint "eagle-import:CAP1206")
      (libsource (lib "eagle-import") (part "CAPACITOR-1206"))
    )
    (comp (ref "C36")
      (value "100uF")
      (footprint "eagle-import:CAP1206")
      (libsource (lib "eagle-import") (part "CAPACITOR-1206"))
    )
    (comp (ref "C37")
      (value "100nF")
      (footprint "eagle-import:CAP0603")
      (libsource (lib "eagle-import") (part "CAPACITOR-0603"))
    )
    (comp (ref "C38")
      (value "10uF")
      (footprint "eagle-import:CAP1206")
      (fields (field (name "VOLTAGE") "50V"))
      (libsource (lib "eagle-import") (part "CAPACITOR-1206"))
    )
    (comp (ref "CON4")
      (value "2EDG-2P-5MM")
      (footprint "eagle-import:2EDG-2P-5MM")
      (libsource (lib "eagle-import") (part "2EDG-2P-5MM"))
    )
    (comp (ref "D2")
      (value "SMAJ24A")
      (footprint "eagle-import:DO214AC")
      (fields (field (name "MF") "Littelfuse"))
      (libsource (lib "eagle-import") (part "SMAJA24"))
    )
    (comp (ref "D3")
      (value "LED0603")
      (footprint "eagle-import:0603")
      (fields (field (name "COLOR") "GREEN"))
      (libsource (lib "eagle-import") (part "LED0603"))
    )
    (comp (ref "F1")
      (value "2.6A Hold")
      (footprint "eagle-import:1206")
      (fields (field (name "HOLD") "3A") (field (name "TRIP") "6A"))
      (libsource (lib "eagle-import") (part "PTC1206"))
    )
    (comp (ref "JP1")
      (value "PINHD-2X5")
      (footprint "eagle-import:2X05")
      (libsource (lib "eagle-import") (part "PINHD-2X5"))
    )
    (comp (ref "L1")
      (value "2.2uH")
      (footprint "eagle-import:IND2520")
      (fields (field (name "CURRENT") "2.2A"))
      (libsource (lib "eagle-import") (part "INDUCTOR-2.5X2X1.2MM"))
    )
    (comp (ref "L20")
      (value "4.7uH")
      (footprint "eagle-import:IND2520")
      (fields (field (name "CURRENT") "1.4A"))
      (libsource (lib "eagle-import") (part "INDUCTOR-2.5X2X1.2MM"))
    )
    (comp (ref "R25")
      (value "100K Ohms")
      (footprint "eagle-import:RES0603")
      (libsource (lib "eagle-import") (part "RESISTOR-0603"))
    )
    (comp (ref "R26")
      (value "10K Ohms")
      (footprint "eagle-import:RES0603")
      (libsource (lib "eagle-import") (part "RESISTOR-0603"))
    )
    (comp (ref "R27")
      (value "100K Ohms")
      (footprint "eagle-import:RES0603")
      (libsource (lib "eagle-import") (part "RESISTOR-0603"))
    )
    (comp (ref "R28")
      (value "75K Ohms")
      (footprint "eagle-import:RES0603")
      (libsource (lib "eagle-import") (part "RESISTOR-0603"))
    )
    (comp (ref "R29")
      (value "41.2K Ohms")
      (footprint "eagle-import:RES0603")
      (libsource (lib "eagle-import") (part "RESISTOR-0603"))
    )
    (comp (ref "R30")
      (value "309K Ohms")
      (footprint "eagle-import:RES0603")
      (libsource (lib "eagle-import") (part "RESISTOR-0603"))
    )
    (comp (ref "R31")
      (value "71.5K Ohms")
      (footprint "eagle-import:RES0603")
      (libsource (lib "eagle-import") (part "RESISTOR-0603"))
    )
    (comp (ref "R32")
      (value "1M Ohms")
      (footprint "eagle-import:RES0603")
      (libsource (lib "eagle-import") (part "RESISTOR-0603"))
    )
    (comp (ref "R33")
      (value "226K Ohms")
      (footprint "eagle-import:RES0603")
      (libsource (lib "eagle-import") (part "RESISTOR-0603"))
    )
    (comp (ref "R34")
      (value "330 Ohms")
      (footprint "eagle-import:RES0603")
      (libsource (lib "eagle-import") (part "RESISTOR-0603"))
    )
    (comp (ref "U5")
      (value "MIC23155")
      (footprint "eagle-import:DFN10")
      (libsource (lib "eagle-import") (part "MIC23155"))
    )
    (comp (ref "U6")
      (value "LT8636")
      (footprint "eagle-import:QFN20_ASYM_CORNER")
      (libsource (lib "eagle-import") (part "LT8636"))
    )
  )
  (nets
    (net (code "1") (name "3V3") (class "Default")
      (node (ref "C1") (pin "1") (pinfunction "C1_1") (pintype "passive"))
      (node (ref "C2") (pin "1") (pinfunction "C1_1") (pintype "passive"))
      (node (ref "C3") (pin "1") (pinfunction "C1_1") (pintype "passive"))
      (node (ref "C34") (pin "1") (pinfunction "C1_1") (pintype "passive"))
      (node (ref "C35") (pin "1") (pinfunction "C1_1") (pintype "passive"))
      (node (ref "C5") (pin "1") (pinfunction "C1_1") (pintype "passive"))
      (node (ref "JP1") (pin "4") (pinfunction "S_4") (pintype "passive"))
      (node (ref "L1") (pin "2") (pinfunction "2_2") (pintype "passive"))
      (node (ref "R1") (pin "2") (pinfunction "2_2") (pintype "passive"))
      (node (ref "R30") (pin "2") (pinfunction "2_2") (pintype "passive"))
      (node (ref "R34") (pin "2") (pinfunction "2_2") (pintype "passive"))
      (node (ref "R39") (pin "2") (pinfunction "2_2") (pintype "passive"))
      (node (ref "R40") (pin "2") (pinfunction "2_2") (pintype "passive"))
      (node (ref "R41") (pin "2") (pinfunction "2_2") (pintype "passive"))
      (node (ref "R42") (pin "2") (pinfunction "2_2") (pintype "passive"))
      (node (ref "R5") (pin "2") (pinfunction "2_2") (pintype "passive"))
      (node (ref "R6") (pin "2") (pinfunction "2_2") (pintype "passive"))
      (node (ref "TC1") (pin "1") (pinfunction "S_1") (pintype "passive"))
      (node (ref "U1") (pin "11") (pinfunction "AVDD_11") (pintype "bidirectional"))
      (node (ref "U1") (pin "14") (pinfunction "IOVDD0_14") (pintype "bidirectional"))
      (node (ref "U1") (pin "15") (pinfunction "AVDD_15") (pintype "bidirectional"))
      (node (ref "U1") (pin "20") (pinfunction "DVDD_20") (pintype "bidirectional"))
      (node (ref "U1") (pin "28") (pinfunction "IOVDD0_28") (pintype "bidirectional"))
      (node (ref "U1") (pin "4") (pinfunction "IOVDD0_4") (pintype "bidirectional"))
      (node (ref "U3") (pin "2") (pinfunction "DVDD_2") (pintype "bidirectional"))
      (node (ref "U3") (pin "8") (pinfunction "~{CNVT}_8") (pintype "bidirectional"))
      (node (ref "U5") (pin "3") (pinfunction "SNS_3") (pintype "bidirectional"))
    )
    (net (code "2") (name "5V0") (class "Default")
      (node (ref "C21") (pin "1") (pinfunction "C1_1") (pintype "passive"))
      (node (ref "C23") (pin "1") (pinfunction "C1_1") (pintype "passive"))
      (node (ref "C26") (pin "1") (pinfunction "C1_1") (pintype "passive"))
      (node (ref "C33") (pin "1") (pinfunction "C1_1") (pintype "passive"))
      (node (ref "C36") (pin "1") (pinfunction "C1_1") (pintype "passive"))
      (node (ref "C37") (pin "1") (pinfunction "C1_1") (pintype "passive"))
      (node (ref "C6") (pin "1") (pinfunction "C1_1") (pintype "passive"))
      (node (ref "C7") (pin "1") (pinfunction "C1_1") (pintype "passive"))
      (node (ref "C8") (pin "1") (pinfunction "C1_1") (pintype "passive"))
      (node (ref "C9") (pin "1") (pinfunction "C1_1") (pintype "passive"))
      (node (ref "JP1") (pin "2") (pinfunction "S_2") (pintype "passive"))
      (node (ref "L20") (pin "2") (pinfunction "2_2") (pintype "passive"))
      (node (ref "R27") (pin "2") (pinfunction "2_2") (pintype "passive"))
      (node (ref "R32") (pin "2") (pinfunction "2_2") (pintype "passive"))
      (node (ref "U2") (pin "4") (pinfunction "~{SHDN}_4") (pintype "bidirectional"))
      (node (ref "U2") (pin "6") (pinfunction "VDD_6") (pintype "bidirectional"))
      (node (ref "U3") (pin "14") (pinfunction "AVDD_14") (pintype "bidirectional"))
      (node (ref "U3") (pin "22") (pinfunction "AVDDIO_22") (pintype "bidirectional"))
      (node (ref "U3") (pin "33") (pinfunction "AVDDIO_33") (pintype "bidirectional"))
      (node (ref "U4") (pin "8") (pinfunction "V+_8") (pintype "power_in"))
      (node (ref "U5") (pin "2") (pinfunction "EN_2") (pintype "bidirectional"))
      (node (ref "U5") (pin "8") (pinfunction "VIN_8") (pintype "bidirectional"))
      (node (ref "U5") (pin "9") (pinfunction "VIN_9") (pintype "bidirectional"))
      (node (ref "U6") (pin "2") (pinfunction "BIAS_2") (pintype "bidirectional"))
    )
    (net (code "3") (name "5V0_VSENSE") (class "Default")
      (node (ref "C25") (pin "1") (pinfunction "C1_1") (pintype "passive"))
      (node (ref "R27") (pin "1") (pinfunction "1_1") (pintype "passive"))
      (node (ref "R28") (pin "2") (pinfunction "2_2") (pintype "passive"))
      (node (ref "U1") (pin "18") (pinfunction "PD6_18") (pintype "bidirectional"))
    )
    (net (code "4") (name "AFE_MISO") (class "Default")
      (node (ref "U1") (pin "30") (pinfunction "PE11_30") (pintype "bidirectional"))
      (node (ref "U3") (pin "6") (pinfunction "DOUT_6") (pintype "bidirectional"))
    )
    (net (code "5") (name "AFE_MOSI") (class "Default")
      (node (ref "U1") (pin "29") (pinfunction "PE10_29") (pintype "bidirectional"))
      (node (ref "U3") (pin "3") (pinfunction "DIN_3") (pintype "bidirectional"))
    )
    (net (code "6") (name "AFE_SCLK") (class "Default")
      (node (ref "U1") (pin "31") (pinfunction "PE12_31") (pintype "bidirectional"))
      (node (ref "U3") (pin "4") (pinfunction "SCLK_4") (pintype "bidirectional"))
    )
    (net (code "7") (name "EN1") (class "Default")
      (node (ref "JP1") (pin "7") (pinfunction "S_7") (pintype "passive"))
      (node (ref "U1") (pin "6") (pinfunction "PC1_6") (pintype "bidirectional"))
    )
    (net (code "8") (name "EN2") (class "Default")
      (node (ref "JP1") (pin "8") (pinfunction "S_8") (pintype "passive"))
      (node (ref "U1") (pin "8") (pinfunction "PB8_8") (pintype "bidirectional"))
    )
    (net (code "9") (name "EN3") (class "Default")
      (node (ref "JP1") (pin "9") (pinfunction "S_9") (pintype "passive"))
      (node (ref "U1") (pin "5") (pinfunction "PC0_5") (pintype "bidirectional"))
    )
    (net (code "10") (name "EN4") (class "Default")
      (node (ref "JP1") (pin "10") (pinfunction "S_10") (pintype "passive"))
      (node (ref "U1") (pin "7") (pinfunction "PB7_7") (pintype "bidirectional"))
    )
    (net (code "11") (name "GND") (class "Default")
      (node (ref "C1") (pin "2") (pinfunction "C2_2") (pintype "passive"))
      (node (ref "C10") (pin "2") (pinfunction "C2_2") (pintype "passive"))
      (node (ref "C11") (pin "2") (pinfunction "C2_2") (pintype "passive"))
      (node (ref "C12") (pin "2") (pinfunction "C2_2") (pintype "passive"))
      (node (ref "C13") (pin "2") (pinfunction "C2_2") (pintype "passive"))
      (node (ref "C14") (pin "2") (pinfunction "C2_2") (pintype "passive"))
      (node (ref "C17") (pin "2") (pinfunction "C2_2") (pintype "passive"))
      (node (ref "C18") (pin "2") (pinfunction "C2_2") (pintype "passive"))
      (node (ref "C19") (pin "2") (pinfunction "C2_2") (pintype "passive"))
      (node (ref "C2") (pin "2") (pinfunction "C2_2") (pintype "passive"))
      (node (ref "C20") (pin "2") (pinfunction "C2_2") (pintype "passive"))
      (node (ref "C21") (pin "2") (pinfunction "C2_2") (pintype "passive"))
      (node (ref "C22") (pin "2") (pinfunction "C2_2") (pintype "passive"))
      (node (ref "C23") (pin "2") (pinfunction "C2_2") (pintype "passive"))
      (node (ref "C24") (pin "2") (pinfunction "C2_2") (pintype "passive"))
      (node (ref "C25") (pin "2") (pinfunction "C2_2") (pintype "passive"))
      (node (ref "C26") (pin "2") (pinfunction "C2_2") (pintype "passive"))
      (node (ref "C27") (pin "2") (pinfunction "C2_2") (pintype "passive"))
      (node (ref "C28") (pin "2") (pinfunction "C2_2") (pintype "passive"))
      (node (ref "C29") (pin "2") (pinfunction "C2_2") (pintype "passive"))
      (node (ref "C3") (pin "2") (pinfunction "C2_2") (pintype "passive"))
      (node (ref "C30") (pin "2") (pinfunction "C2_2") (pintype "passive"))
      (node (ref "C31") (pin "2") (pinfunction "C2_2") (pintype "passive"))
      (node (ref "C34") (pin "2") (pinfunction "C2_2") (pintype "passive"))
      (node (ref "C35") (pin "2") (pinfunction "C2_2") (pintype "passive"))
      (node (ref "C36") (pin "2") (pinfunction "C2_2") (pintype "passive"))
      (node (ref "C37") (pin "2") (pinfunction "C2_2") (pintype "passive"))
      (node (ref "C38") (pin "2") (pinfunction "C2_2") (pintype "passive"))
      (node (ref "C39") (pin "2") (pinfunction "C2_2") (pintype "passive"))
      (node (ref "C4") (pin "2") (pinfunction "C2_2") (pintype "passive"))
      (node (ref "C40") (pin "2") (pinfunction "C2_2") (pintype "passive"))
      (node (ref "C41") (pin "2") (pinfunction "C2_2") (pintype "passive"))
      (node (ref "C42") (pin "2") (pinfunction "C2_2") (pintype "passive"))
      (node (ref "C43") (pin "2") (pinfunction "C2_2") (pintype "passive"))
      (node (ref "C44") (pin "2") (pinfunction "C2_2") (pintype "passive"))
      (node (ref "C45") (pin "2") (pinfunction "C2_2") (pintype "passive"))
      (node (ref "C46") (pin "2") (pinfunction "C2_2") (pintype "passive"))
      (node (ref "C5") (pin "2") (pinfunction "C2_2") (pintype "passive"))
      (node (ref "C6") (pin "2") (pinfunction "C2_2") (pintype "passive"))
      (node (ref "C7") (pin "2") (pinfunction "C2_2") (pintype "passive"))
      (node (ref "C8") (pin "2") (pinfunction "C2_2") (pintype "passive"))
      (node (ref "C9") (pin "2") (pinfunction "C2_2") (pintype "passive"))
      (node (ref "CON1") (pin "3") (pinfunction "S_3") (pintype "passive"))
      (node (ref "CON2") (pin "P$3") (pinfunction "S_P$3") (pintype "passive"))
      (node (ref "CON3") (pin "P$3") (pinfunction "S_P$3") (pintype "passive"))
      (node (ref "CON4") (pin "P$1") (pinfunction "S_P$1") (pintype "passive"))
      (node (ref "D1") (pin "C") (pinfunction "C_C") (pintype "passive"))
      (node (ref "D2") (pin "A") (pinfunction "A_A") (pintype "passive"))
      (node (ref "D3") (pin "C") (pinfunction "C_C") (pintype "passive"))
      (node (ref "JP1") (pin "1") (pinfunction "S_1") (pintype "passive"))
      (node (ref "JP1") (pin "3") (pinfunction "S_3") (pintype "passive"))
      (node (ref "R10") (pin "1") (pinfunction "1_1") (pintype "passive"))
      (node (ref "R26") (pin "1") (pinfunction "1_1") (pintype "passive"))
      (node (ref "R28") (pin "1") (pinfunction "1_1") (pintype "passive"))
      (node (ref "R29") (pin "1") (pinfunction "1_1") (pintype "passive"))
      (node (ref "R31") (pin "1") (pinfunction "1_1") (pintype "passive"))
      (node (ref "R33") (pin "1") (pinfunction "1_1") (pintype "passive"))
      (node (ref "R36") (pin "1") (pinfunction "1_1") (pintype "passive"))
      (node (ref "R38") (pin "1") (pinfunction "1_1") (pintype "passive"))
      (node (ref "R8") (pin "1") (pinfunction "1_1") (pintype "passive"))
      (node (ref "RFCON1") (pin "1") (pinfunction "GND_1") (pintype "bidirectional"))
      (node (ref "RFCON1") (pin "3") (pinfunction "GND_3") (pintype "bidirectional"))
      (node (ref "RFCON1") (pin "4") (pinfunction "GND_4") (pintype "bidirectional"))
      (node (ref "RFCON2") (pin "1") (pinfunction "GND_1") (pintype "bidirectional"))
      (node (ref "RFCON2") (pin "3") (pinfunction "GND_3") (pintype "bidirectional"))
      (node (ref "RFCON2") (pin "4") (pinfunction "GND_4") (pintype "bidirectional"))
      (node (ref "TC1") (pin "3") (pinfunction "S_3") (pintype "passive"))
      (node (ref "U1") (pin "33") (pinfunction "VSS_33") (pintype "bidirectional"))
      (node (ref "U2") (pin "2") (pinfunction "GND_2") (pintype "bidirectional"))
      (node (ref "U2") (pin "3") (pinfunction "GND_3") (pintype "bidirectional"))
      (node (ref "U2") (pin "5") (pinfunction "GND_5") (pintype "bidirectional"))
      (node (ref "U3") (pin "1") (pinfunction "DGND_1") (pintype "bidirectional"))
      (node (ref "U3") (pin "15") (pinfunction "AGND_15") (pintype "bidirectional"))
      (node (ref "U3") (pin "32") (pinfunction "AGND_32") (pintype "bidirectional"))
      (node (ref "U3") (pin "41") (pinfunction "AVSSIO_41") (pintype "bidirectional"))
      (node (ref "U4") (pin "5") (pinfunction "V-_5") (pintype "power_in"))
      (node (ref "U5") (pin "10") (pinfunction "PGND_10") (pintype "bidirectional"))
      (node (ref "U5") (pin "11") (pinfunction "PGND_11") (pintype "bidirectional"))
      (node (ref "U5") (pin "7") (pinfunction "AGND_7") (pintype "bidirectional"))
      (node (ref "U6") (pin "12") (pinfunction "GND_12") (pintype "bidirectional"))
      (node (ref "U6") (pin "13") (pinfunction "GND_13") (pintype "bidirectional"))
      (node (ref "U6") (pin "21") (pinfunction "GND_21") (pintype "bidirectional"))
      (node (ref "U6") (pin "4") (pinfunction "GND_4") (pintype "bidirectional"))
      (node (ref "U6") (pin "5") (pinfunction "GND_5") (pintype "bidirectional"))
      (node (ref "U6") (pin "M1") (pinfunction "GND_M1") (pintype "bidirectional"))
      (node (ref "U6") (pin "M2") (pinfunction "GND_M2") (pintype "bidirectional"))
      (node (ref "U6") (pin "M3") (pinfunction "GND_M3") (pintype "bidirectional"))
      (node (ref "U6") (pin "M4") (pinfunction "GND_M4") (pintype "bidirectional"))
    )
    (net (code "12") (name "I2C0_SCL") (class "Default")
      (node (ref "R3") (pin "2") (pinfunction "2_2") (pintype "passive"))
      (node (ref "R39") (pin "1") (pinfunction "1_1") (pintype "passive"))
      (node (ref "U1") (pin "2") (pinfunction "PA1_2") (pintype "bidirectional"))
    )
    (net (code "13") (name "I2C0_SDA") (class "Default")
      (node (ref "R2") (pin "2") (pinfunction "2_2") (pintype "passive"))
      (node (ref "R40") (pin "1") (pinfunction "1_1") (pintype "passive"))
      (node (ref "U1") (pin "1") (pinfunction "PA0_1") (pintype "bidirectional"))
    )
    (net (code "14") (name "I2C1_SCL") (class "Default")
      (node (ref "JP1") (pin "6") (pinfunction "S_6") (pintype "passive"))
      (node (ref "R41") (pin "1") (pinfunction "1_1") (pintype "passive"))
      (node (ref "U1") (pin "17") (pinfunction "PD5_17") (pintype "bidirectional"))
    )
    (net (code "15") (name "I2C1_SDA") (class "Default")
      (node (ref "JP1") (pin "5") (pinfunction "S_5") (pintype "passive"))
      (node (ref "R42") (pin "1") (pinfunction "1_1") (pintype "passive"))
      (node (ref "U1") (pin "16") (pinfunction "PD4_16") (pintype "bidirectional"))
    )
    (net (code "16") (name "LED") (class "Default")
      (node (ref "R4") (pin "2") (pinfunction "2_2") (pintype "passive"))
      (node (ref "U1") (pin "24") (pinfunction "PC15_24") (pintype "bidirectional"))
    )
    (net (code "17") (name "Net-(C4-C1)") (class "Default")
      (node (ref "C4") (pin "1") (pinfunction "C1_1") (pintype "passive"))
      (node (ref "U1") (pin "21") (pinfunction "DECOUPLE_21") (pintype "bidirectional"))
    )
    (net (code "18") (name "Net-(C10-C1)") (class "Default")
      (node (ref "C10") (pin "1") (pinfunction "C1_1") (pintype "passive"))
      (node (ref "U2") (pin "1") (pinfunction "VOUT_1") (pintype "bidirectional"))
      (node (ref "U3") (pin "10") (pinfunction "ADC_EXT_REF_10") (pintype "bidirectional"))
    )
    (net (code "19") (name "Net-(C11-C1)") (class "Default")
      (node (ref "C11") (pin "1") (pinfunction "C1_1") (pintype "passive"))
      (node (ref "U3") (pin "9") (pinfunction "ADC_INT_REF_9") (pintype "bidirectional"))
    )
    (net (code "20") (name "Net-(C12-C1)") (class "Default")
      (node (ref "C12") (pin "1") (pinfunction "C1_1") (pintype "passive"))
      (node (ref "U3") (pin "11") (pinfunction "DAC_REF_11") (pintype "bidirectional"))
    )
    (net (code "21") (name "Net-(C15-C1)") (class "Default")
      (node (ref "C15") (pin "1") (pinfunction "C1_1") (pintype "passive"))
      (node (ref "R11") (pin "1") (pinfunction "1_1") (pintype "passive"))
      (node (ref "U4") (pin "2") (pinfunction "-IN_2") (pintype "input"))
    )
    (net (code "22") (name "Net-(C15-C2)") (class "Default")
      (node (ref "C15") (pin "2") (pinfunction "C2_2") (pintype "passive"))
      (node (ref "R19") (pin "1") (pinfunction "1_1") (pintype "passive"))
      (node (ref "U4") (pin "1") (pinfunction "+IN_1") (pintype "input"))
    )
    (net (code "23") (name "Net-(C16-C1)") (class "Default")
      (node (ref "C16") (pin "1") (pinfunction "C1_1") (pintype "passive"))
      (node (ref "R12") (pin "1") (pinfunction "1_1") (pintype "passive"))
      (node (ref "U4") (pin "4") (pinfunction "-IN_4") (pintype "input"))
    )
    (net (code "24") (name "Net-(C16-C2)") (class "Default")
      (node (ref "C16") (pin "2") (pinfunction "C2_2") (pintype "passive"))
      (node (ref "R20") (pin "1") (pinfunction "1_1") (pintype "passive"))
      (node (ref "U4") (pin "3") (pinfunction "+IN_3") (pintype "input"))
    )
    (net (code "25") (name "Net-(C17-C1)") (class "Default")
      (node (ref "C17") (pin "1") (pinfunction "C1_1") (pintype "passive"))
      (node (ref "R21") (pin "1") (pinfunction "1_1") (pintype "passive"))
      (node (ref "R23") (pin "2") (pinfunction "2_2") (pintype "passive"))
    )
    (net (code "26") (name "Net-(C18-C1)") (class "Default")
      (node (ref "C18") (pin "1") (pinfunction "C1_1") (pintype "passive"))
      (node (ref "R22") (pin "1") (pinfunction "1_1") (pintype "passive"))
      (node (ref "R24") (pin "2") (pinfunction "2_2") (pintype "passive"))
    )
    (net (code "27") (name "Net-(C28-C1)") (class "Default")
      (node (ref "C28") (pin "1") (pinfunction "C1_1") (pintype "passive"))
      (node (ref "U5") (pin "6") (pinfunction "SS_6") (pintype "bidirectional"))
    )
    (net (code "28") (name "Net-(C30-C1)") (class "Default")
      (node (ref "C30") (pin "1") (pinfunction "C1_1") (pintype "passive"))
      (node (ref "U6") (pin "15") (pinfunction "SYNC/MODE_15") (pintype "bidirectional"))
      (node (ref "U6") (pin "3") (pinfunction "INTVCC_3") (pintype "bidirectional"))
    )
    (net (code "29") (name "Net-(C31-C1)") (class "Default")
      (node (ref "C31") (pin "1") (pinfunction "C1_1") (pintype "passive"))
      (node (ref "U6") (pin "18") (pinfunction "TR/SS_18") (pintype "bidirectional"))
    )
    (net (code "30") (name "Net-(C32-C1)") (class "Default")
      (node (ref "C32") (pin "1") (pinfunction "C1_1") (pintype "passive"))
      (node (ref "L20") (pin "1") (pinfunction "1_1") (pintype "passive"))
      (node (ref "U6") (pin "10") (pinfunction "SW_10") (pintype "bidirectional"))
      (node (ref "U6") (pin "8") (pinfunction "SW_8") (pintype "bidirectional"))
      (node (ref "U6") (pin "9") (pinfunction "SW_9") (pintype "bidirectional"))
    )
    (net (code "31") (name "Net-(C32-C2)") (class "Default")
      (node (ref "C32") (pin "2") (pinfunction "C2_2") (pintype "passive"))
      (node (ref "U6") (pin "7") (pinfunction "BST_7") (pintype "bidirectional"))
    )
    (net (code "32") (name "Net-(C33-C2)") (class "Default")
      (node (ref "C33") (pin "2") (pinfunction "C2_2") (pintype "passive"))
      (node (ref "R32") (pin "1") (pinfunction "1_1") (pintype "passive"))
      (node (ref "R33") (pin "2") (pinfunction "2_2") (pintype "passive"))
      (node (ref "U6") (pin "19") (pinfunction "FB_19") (pintype "bidirectional"))
      (node (ref "U6") (pin "20") (pinfunction "FB_20") (pintype "bidirectional"))
    )
    (net (code "33") (name "Net-(C40-C1)") (class "Default")
      (node (ref "C40") (pin "1") (pinfunction "C1_1") (pintype "passive"))
      (node (ref "CON3") (pin "P$4") (pinfunction "S_P$4") (pintype "passive"))
      (node (ref "CON3") (pin "P$5") (pinfunction "S_P$5") (pintype "passive"))
      (node (ref "R12") (pin "2") (pinfunction "2_2") (pintype "passive"))
      (node (ref "R16") (pin "2") (pinfunction "2_2") (pintype "passive"))
      (node (ref "R17") (pin "2") (pinfunction "2_2") (pintype "passive"))
      (node (ref "R18") (pin "2") (pinfunction "2_2") (pintype "passive"))
      (node (ref "R9") (pin "2") (pinfunction "2_2") (pintype "passive"))
    )
    (net (code "34") (name "Net-(C41-C1)") (class "Default")
      (node (ref "C41") (pin "1") (pinfunction "C1_1") (pintype "passive"))
      (node (ref "L4") (pin "2") (pinfunction "2_2") (pintype "passive"))
      (node (ref "L5") (pin "1") (pinfunction "1_1") (pintype "passive"))
    )
    (net (code "35") (name "Net-(C44-C1)") (class "Default")
      (node (ref "C44") (pin "1") (pinfunction "C1_1") (pintype "passive"))
      (node (ref "CON2") (pin "P$4") (pinfunction "S_P$4") (pintype "passive"))
      (node (ref "CON2") (pin "P$5") (pinfunction "S_P$5") (pintype "passive"))
      (node (ref "R11") (pin "2") (pinfunction "2_2") (pintype "passive"))
      (node (ref "R13") (pin "2") (pinfunction "2_2") (pintype "passive"))
      (node (ref "R14") (pin "2") (pinfunction "2_2") (pintype "passive"))
      (node (ref "R15") (pin "2") (pinfunction "2_2") (pintype "passive"))
      (node (ref "R7") (pin "2") (pinfunction "2_2") (pintype "passive"))
    )
    (net (code "36") (name "Net-(C45-C1)") (class "Default")
      (node (ref "C45") (pin "1") (pinfunction "C1_1") (pintype "passive"))
      (node (ref "L7") (pin "2") (pinfunction "2_2") (pintype "passive"))
      (node (ref "L8") (pin "1") (pinfunction "1_1") (pintype "passive"))
    )
    (net (code "37") (name "Net-(CON1A-S)") (class "Default")
      (node (ref "CON1") (pin "1") (pinfunction "S_1") (pintype "passive"))
      (node (ref "R2") (pin "1") (pinfunction "1_1") (pintype "passive"))
    )
    (net (code "38") (name "Net-(CON1B-S)") (class "Default")
      (node (ref "CON1") (pin "2") (pinfunction "S_2") (pintype "passive"))
      (node (ref "R3") (pin "1") (pinfunction "1_1") (pintype "passive"))
    )
    (net (code "39") (name "Net-(CON2A-S)") (class "Default")
      (node (ref "CON2") (pin "P$1") (pinfunction "S_P$1") (pintype "passive"))
      (node (ref "CON2") (pin "P$2") (pinfunction "S_P$2") (pintype "passive"))
      (node (ref "R13") (pin "1") (pinfunction "1_1") (pintype "passive"))
      (node (ref "R14") (pin "1") (pinfunction "1_1") (pintype "passive"))
      (node (ref "R15") (pin "1") (pinfunction "1_1") (pintype "passive"))
      (node (ref "R19") (pin "2") (pinfunction "2_2") (pintype "passive"))
    )
    (net (code "40") (name "Net-(CON3A-S)") (class "Default")
      (node (ref "CON3") (pin "P$1") (pinfunction "S_P$1") (pintype "passive"))
      (node (ref "CON3") (pin "P$2") (pinfunction "S_P$2") (pintype "passive"))
      (node (ref "R16") (pin "1") (pinfunction "1_1") (pintype "passive"))
      (node (ref "R17") (pin "1") (pinfunction "1_1") (pintype "passive"))
      (node (ref "R18") (pin "1") (pinfunction "1_1") (pintype "passive"))
      (node (ref "R20") (pin "2") (pinfunction "2_2") (pintype "passive"))
    )
    (net (code "41") (name "Net-(CON4B-S)") (class "Default")
      (node (ref "CON4") (pin "P$2") (pinfunction "S_P$2") (pintype "passive"))
      (node (ref "F1") (pin "2") (pinfunction "2_2") (pintype "passive"))
    )
    (net (code "42") (name "Net-(D1-PadA)") (class "Default")
      (node (ref "D1") (pin "A") (pinfunction "A_A") (pintype "passive"))
      (node (ref "R4") (pin "1") (pinfunction "1_1") (pintype "passive"))
    )
    (net (code "43") (name "Net-(D3-PadA)") (class "Default")
      (node (ref "D3") (pin "A") (pinfunction "A_A") (pintype "passive"))
      (node (ref "R34") (pin "1") (pinfunction "1_1") (pintype "passive"))
    )
    (net (code "44") (name "Net-(U4A-OUT)") (class "Default")
      (node (ref "R21") (pin "2") (pinfunction "2_2") (pintype "passive"))
      (node (ref "U4") (pin "7") (pinfunction "OUT_7") (pintype "output"))
    )
    (net (code "45") (name "Net-(U4B-OUT)") (class "Default")
      (node (ref "R22") (pin "2") (pinfunction "2_2") (pintype "passive"))
      (node (ref "U4") (pin "6") (pinfunction "OUT_6") (pintype "output"))
    )
    (net (code "46") (name "Net-(U5-FB)") (class "Default")
      (node (ref "R30") (pin "1") (pinfunction "1_1") (pintype "passive"))
      (node (ref "R31") (pin "2") (pinfunction "2_2") (pintype "passive"))
      (node (ref "U5") (pin "4") (pinfunction "FB_4") (pintype "bidirectional"))
    )
    (net (code "47") (name "Net-(U5-SW)") (class "Default")
      (node (ref "L1") (pin "1") (pinfunction "1_1") (pintype "passive"))
      (node (ref "U5") (pin "1") (pinfunction "SW_1") (pintype "bidirectional"))
    )
    (net (code "48") (name "Net-(U6-RT)") (class "Default")
      (node (ref "R29") (pin "2") (pinfunction "2_2") (pintype "passive"))
      (node (ref "U6") (pin "17") (pinfunction "RT_17") (pintype "bidirectional"))
    )
    (net (code "49") (name "PA1_VG") (class "Default")
      (node (ref "C42") (pin "1") (pinfunction "C1_1") (pintype "passive"))
      (node (ref "L5") (pin "2") (pinfunction "2_2") (pintype "passive"))
      (node (ref "R36") (pin "2") (pinfunction "2_2") (pintype "passive"))
      (node (ref "RFCON2") (pin "2") (pinfunction "SIGNAL_2") (pintype "bidirectional"))
    )
    (net (code "50") (name "PA1_VG_EN") (class "Default")
      (node (ref "U1") (pin "13") (pinfunction "PB14_13") (pintype "bidirectional"))
      (node (ref "U3") (pin "16") (pinfunction "PORT0_16") (pintype "bidirectional"))
    )
    (net (code "51") (name "PA1_VG_FLT") (class "Default")
      (node (ref "C39") (pin "1") (pinfunction "C1_1") (pintype "passive"))
      (node (ref "R35") (pin "1") (pinfunction "1_1") (pintype "passive"))
      (node (ref "U3") (pin "24") (pinfunction "PORT5_24") (pintype "bidirectional"))
    )
    (net (code "52") (name "PA1_VG_RAW") (class "Default")
      (node (ref "R35") (pin "2") (pinfunction "2_2") (pintype "passive"))
      (node (ref "U3") (pin "23") (pinfunction "PORT4_23") (pintype "bidirectional"))
    )
    (net (code "53") (name "PA1_VG_SW") (class "Default")
      (node (ref "L4") (pin "1") (pinfunction "1_1") (pintype "passive"))
      (node (ref "U3") (pin "25") (pinfunction "PORT6_25") (pintype "bidirectional"))
    )
    (net (code "54") (name "PA2_VG") (class "Default")
      (node (ref "C46") (pin "1") (pinfunction "C1_1") (pintype "passive"))
      (node (ref "L8") (pin "2") (pinfunction "2_2") (pintype "passive"))
      (node (ref "R38") (pin "2") (pinfunction "2_2") (pintype "passive"))
      (node (ref "RFCON1") (pin "2") (pinfunction "SIGNAL_2") (pintype "bidirectional"))
    )
    (net (code "55") (name "PA2_VG_EN") (class "Default")
      (node (ref "U1") (pin "12") (pinfunction "PB13_12") (pintype "bidirectional"))
      (node (ref "U3") (pin "17") (pinfunction "PORT1_17") (pintype "bidirectional"))
    )
    (net (code "56") (name "PA2_VG_FLT") (class "Default")
      (node (ref "C43") (pin "1") (pinfunction "C1_1") (pintype "passive"))
      (node (ref "R37") (pin "1") (pinfunction "1_1") (pintype "passive"))
      (node (ref "U3") (pin "28") (pinfunction "PORT9_28") (pintype "bidirectional"))
    )
    (net (code "57") (name "PA2_VG_RAW") (class "Default")
      (node (ref "R37") (pin "2") (pinfunction "2_2") (pintype "passive"))
      (node (ref "U3") (pin "27") (pinfunction "PORT8_27") (pintype "bidirectional"))
    )
    (net (code "58") (name "PA2_VG_SW") (class "Default")
      (node (ref "L7") (pin "1") (pinfunction "1_1") (pintype "passive"))
      (node (ref "U3") (pin "29") (pinfunction "PORT10_29") (pintype "bidirectional"))
    )
    (net (code "59") (name "SWCLK") (class "Default")
      (node (ref "TC1") (pin "4") (pinfunction "S_4") (pintype "passive"))
      (node (ref "U1") (pin "25") (pinfunction "PF0_25") (pintype "bidirectional"))
    )
    (net (code "60") (name "SWDIO") (class "Default")
      (node (ref "TC1") (pin "2") (pinfunction "S_2") (pintype "passive"))
      (node (ref "U1") (pin "26") (pinfunction "PF1_26") (pintype "bidirectional"))
    )
    (net (code "61") (name "SWO") (class "Default")
      (node (ref "TC1") (pin "6") (pinfunction "S_6") (pintype "passive"))
      (node (ref "U1") (pin "27") (pinfunction "PF2_27") (pintype "bidirectional"))
    )
    (net (code "62") (name "TEMP0N") (class "Default")
      (node (ref "CON5") (pin "2") (pinfunction "S_2") (pintype "passive"))
      (node (ref "U3") (pin "13") (pinfunction "D0N_13") (pintype "bidirectional"))
    )
    (net (code "63") (name "TEMP0P") (class "Default")
      (node (ref "CON5") (pin "1") (pinfunction "S_1") (pintype "passive"))
      (node (ref "U3") (pin "12") (pinfunction "D0P_12") (pintype "bidirectional"))
    )
    (net (code "64") (name "TEMP1N") (class "Default")
      (node (ref "CON6") (pin "2") (pinfunction "S_2") (pintype "passive"))
      (node (ref "U3") (pin "20") (pinfunction "D1N_20") (pintype "bidirectional"))
    )
    (net (code "65") (name "TEMP1P") (class "Default")
      (node (ref "CON6") (pin "1") (pinfunction "S_1") (pintype "passive"))
      (node (ref "U3") (pin "19") (pinfunction "D1P_19") (pintype "bidirectional"))
    )
    (net (code "66") (name "VIN") (class "Default")
      (node (ref "C22") (pin "1") (pinfunction "C1_1") (pintype "passive"))
      (node (ref "C27") (pin "1") (pinfunction "C1_1") (pintype "passive"))
      (node (ref "C29") (pin "1") (pinfunction "C1_1") (pintype "passive"))
      (node (ref "C38") (pin "1") (pinfunction "C1_1") (pintype "passive"))
      (node (ref "D2") (pin "C") (pinfunction "C_C") (pintype "passive"))
      (node (ref "F1") (pin "1") (pinfunction "1_1") (pintype "passive"))
      (node (ref "R25") (pin "2") (pinfunction "2_2") (pintype "passive"))
      (node (ref "U6") (pin "11") (pinfunction "VIN_11") (pintype "bidirectional"))
      (node (ref "U6") (pin "14") (pinfunction "EN/UV_14") (pintype "bidirectional"))
      (node (ref "U6") (pin "6") (pinfunction "VIN_6") (pintype "bidirectional"))
    )
    (net (code "67") (name "VIN_VSENSE") (class "Default")
      (node (ref "C24") (pin "1") (pinfunction "C1_1") (pintype "passive"))
      (node (ref "R25") (pin "1") (pinfunction "1_1") (pintype "passive"))
      (node (ref "R26") (pin "2") (pinfunction "2_2") (pintype "passive"))
      (node (ref "U1") (pin "19") (pinfunction "PD7_19") (pintype "bidirectional"))
    )
    (net (code "68") (name "VPA1_ID_SENSE") (class "Default")
      (node (ref "C19") (pin "1") (pinfunction "C1_1") (pintype "passive"))
      (node (ref "R23") (pin "1") (pinfunction "1_1") (pintype "passive"))
      (node (ref "U3") (pin "39") (pinfunction "PORT18_39") (pintype "bidirectional"))
    )
    (net (code "69") (name "VPA1_VD_SENSE") (class "Default")
      (node (ref "C13") (pin "1") (pinfunction "C1_1") (pintype "passive"))
      (node (ref "R7") (pin "1") (pinfunction "1_1") (pintype "passive"))
      (node (ref "R8") (pin "2") (pinfunction "2_2") (pintype "passive"))
      (node (ref "U3") (pin "35") (pinfunction "PORT14_35") (pintype "bidirectional"))
    )
    (net (code "70") (name "VPA2_ID_SENSE") (class "Default")
      (node (ref "C20") (pin "1") (pinfunction "C1_1") (pintype "passive"))
      (node (ref "R24") (pin "1") (pinfunction "1_1") (pintype "passive"))
      (node (ref "U3") (pin "40") (pinfunction "PORT19_40") (pintype "bidirectional"))
    )
    (net (code "71") (name "VPA2_VD_SENSE") (class "Default")
      (node (ref "C14") (pin "1") (pinfunction "C1_1") (pintype "passive"))
      (node (ref "R10") (pin "2") (pinfunction "2_2") (pintype "passive"))
      (node (ref "R9") (pin "1") (pinfunction "1_1") (pintype "passive"))
      (node (ref "U3") (pin "36") (pinfunction "PORT15_36") (pintype "bidirectional"))
    )
    (net (code "72") (name "unconnected-(TC1F-S-Pad5)") (class "Default")
      (node (ref "TC1") (pin "5") (pinfunction "S_5") (pintype "passive"))
    )
    (net (code "73") (name "unconnected-(U1-PB11-Pad10)") (class "Default")
      (node (ref "U1") (pin "10") (pinfunction "PB11_10") (pintype "bidirectional"))
    )
    (net (code "74") (name "unconnected-(U1-PC13-Pad22)") (class "Default")
      (node (ref "U1") (pin "22") (pinfunction "PC13_22") (pintype "bidirectional"))
    )
    (net (code "75") (name "unconnected-(U1-PC14-Pad23)") (class "Default")
      (node (ref "U1") (pin "23") (pinfunction "PC14_23") (pintype "bidirectional"))
    )
    (net (code "76") (name "unconnected-(U3-PORT2-Pad18)") (class "Default")
      (node (ref "U3") (pin "18") (pinfunction "PORT2_18") (pintype "bidirectional"))
    )
    (net (code "77") (name "unconnected-(U3-PORT3-Pad21)") (class "Default")
      (node (ref "U3") (pin "21") (pinfunction "PORT3_21") (pintype "bidirectional"))
    )
    (net (code "78") (name "unconnected-(U3-PORT7-Pad26)") (class "Default")
      (node (ref "U3") (pin "26") (pinfunction "PORT7_26") (pintype "bidirectional"))
    )
    (net (code "79") (name "unconnected-(U3-PORT11-Pad30)") (class "Default")
      (node (ref "U3") (pin "30") (pinfunction "PORT11_30") (pintype "bidirectional"))
    )
    (net (code "80") (name "unconnected-(U3-PORT12-Pad31)") (class "Default")
      (node (ref "U3") (pin "31") (pinfunction "PORT12_31") (pintype "bidirectional"))
    )
    (net (code "81") (name "unconnected-(U3-PORT13-Pad34)") (class "Default")
      (node (ref "U3") (pin "34") (pinfunction "PORT13_34") (pintype "bidirectional"))
    )
    (net (code "82") (name "unconnected-(U3-PORT16-Pad37)") (class "Default")
      (node (ref "U3") (pin "37") (pinfunction "PORT16_37") (pintype "bidirectional"))
    )
    (net (code "83") (name "unconnected-(U3-PORT17-Pad38)") (class "Default")
      (node (ref "U3") (pin "38") (pinfunction "PORT17_38") (pintype "bidirectional"))
    )
    (net (code "84") (name "unconnected-(U5-PG-Pad5)") (class "Default")
      (node (ref "U5") (pin "5") (pinfunction "PG_5") (pintype "bidirectional"))
    )
    (net (code "85") (name "unconnected-(U6-CLKOUT-Pad16)") (class "Default")
      (node (ref "U6") (pin "16") (pinfunction "CLKOUT_16") (pintype "bidirectional"))
    )
    (net (code "86") (name "unconnected-(U6-PG-Pad1)") (class "Default")
      (node (ref "U6") (pin "1") (pinfunction "PG_1") (pintype "bidirectional"))
    )
    (net (code "87") (name "~{AFE_CS}") (class "Default")
      (node (ref "R5") (pin "1") (pinfunction "1_1") (pintype "passive"))
      (node (ref "U1") (pin "32") (pinfunction "PE13_32") (pintype "bidirectional"))
      (node (ref "U3") (pin "5") (pinfunction "~{CS}_5") (pintype "bidirectional"))
    )
    (net (code "88") (name "~{AFE_IRQ}") (class "Default")
      (node (ref "R6") (pin "1") (pinfunction "1_1") (pintype "passive"))
      (node (ref "U1") (pin "3") (pinfunction "PA2_3") (pintype "bidirectional"))
      (node (ref "U3") (pin "7") (pinfunction "~{INT}_7") (pintype "bidirectional"))
    )
    (net (code "89") (name "~{RESET}") (class "Default")
      (node (ref "R1") (pin "1") (pinfunction "1_1") (pintype "passive"))
      (node (ref "TC1") (pin "10") (pinfunction "S_10") (pintype "passive"))
      (node (ref "U1") (pin "9") (pinfunction "~{RESET}_9") (pintype "bidirectional"))
    )
  )
)
